# Amplifier.net
KiCad netlist of a schematic drawn in Altium Designer
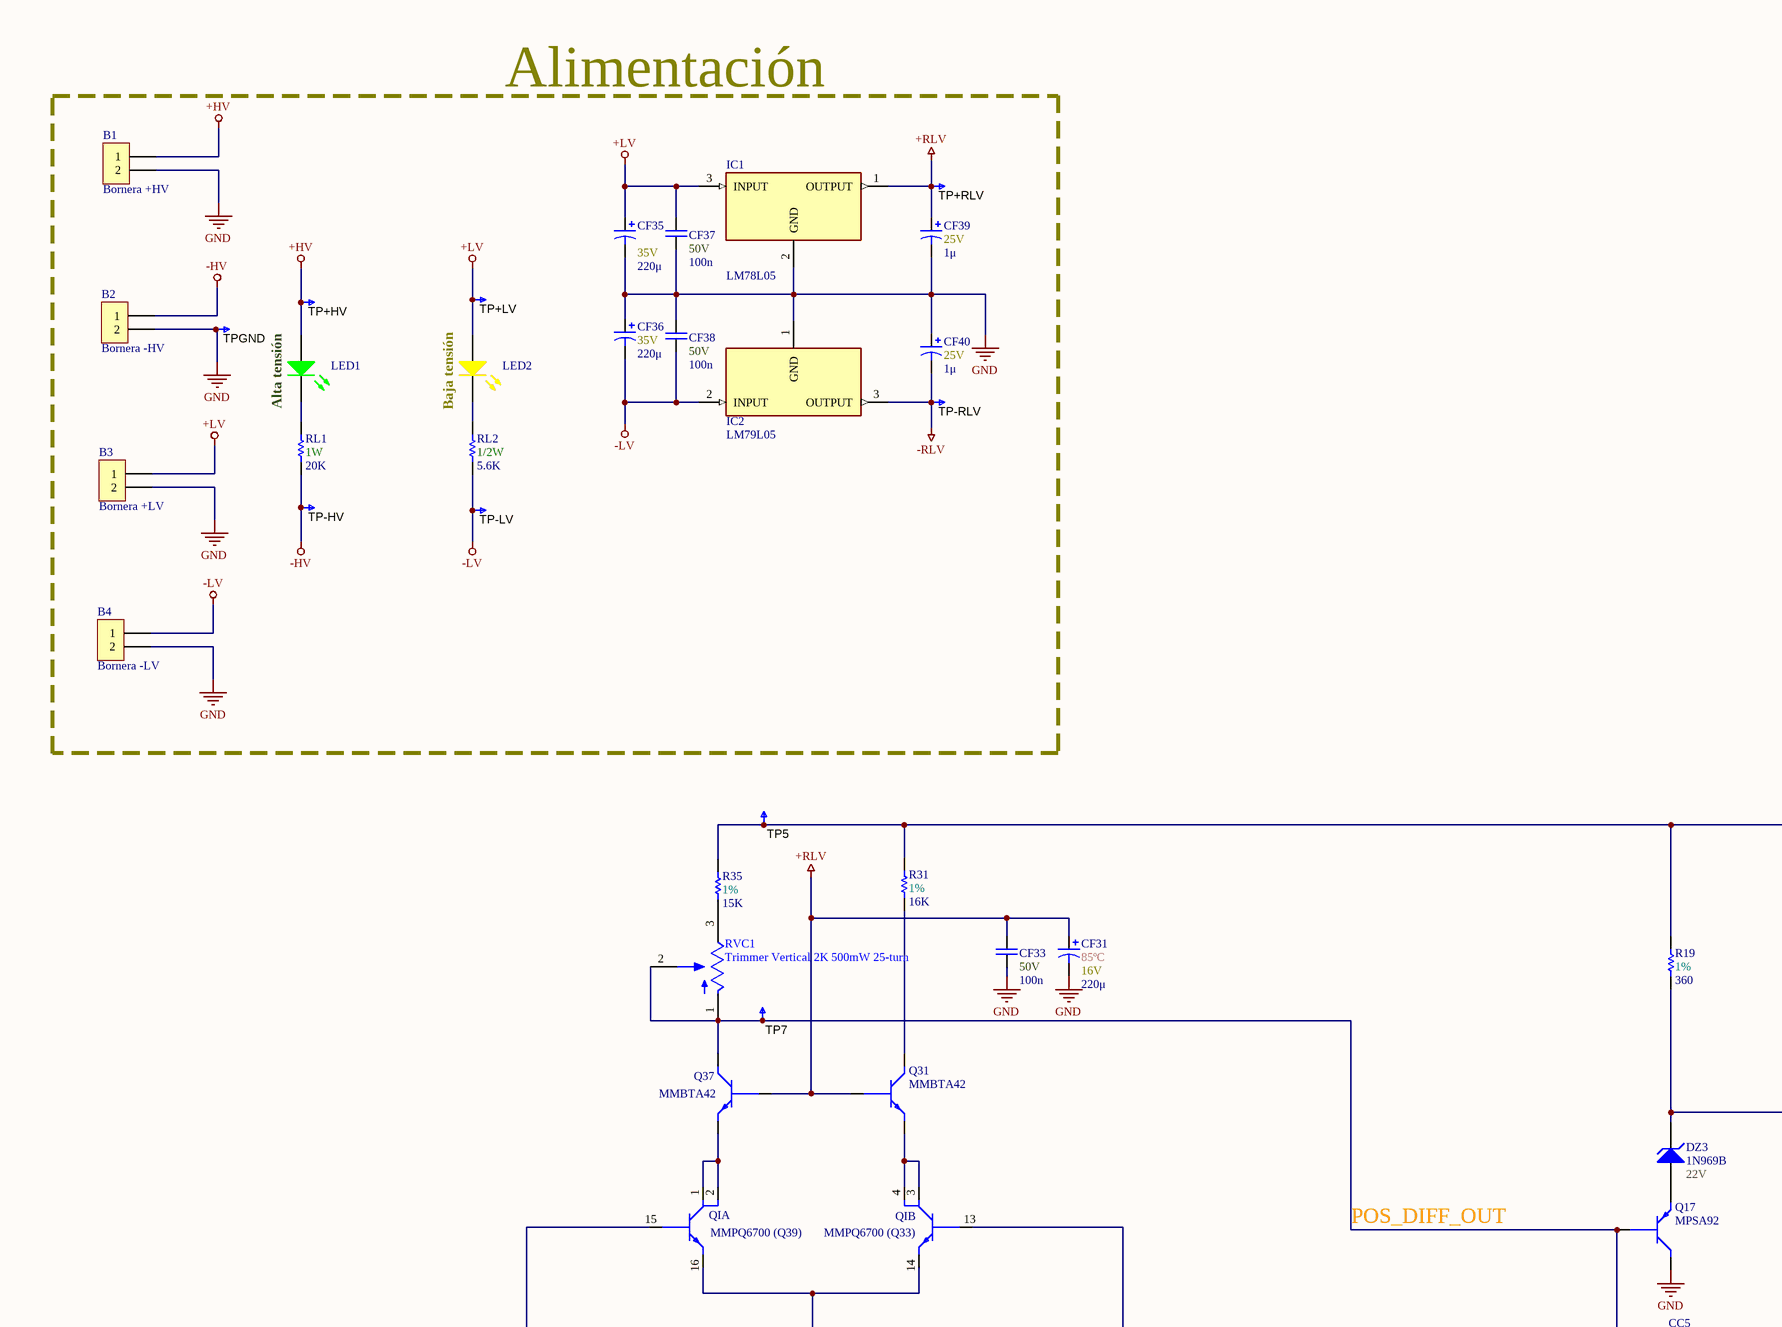
[diagram p0: Amplifier.SchDoc, top left]
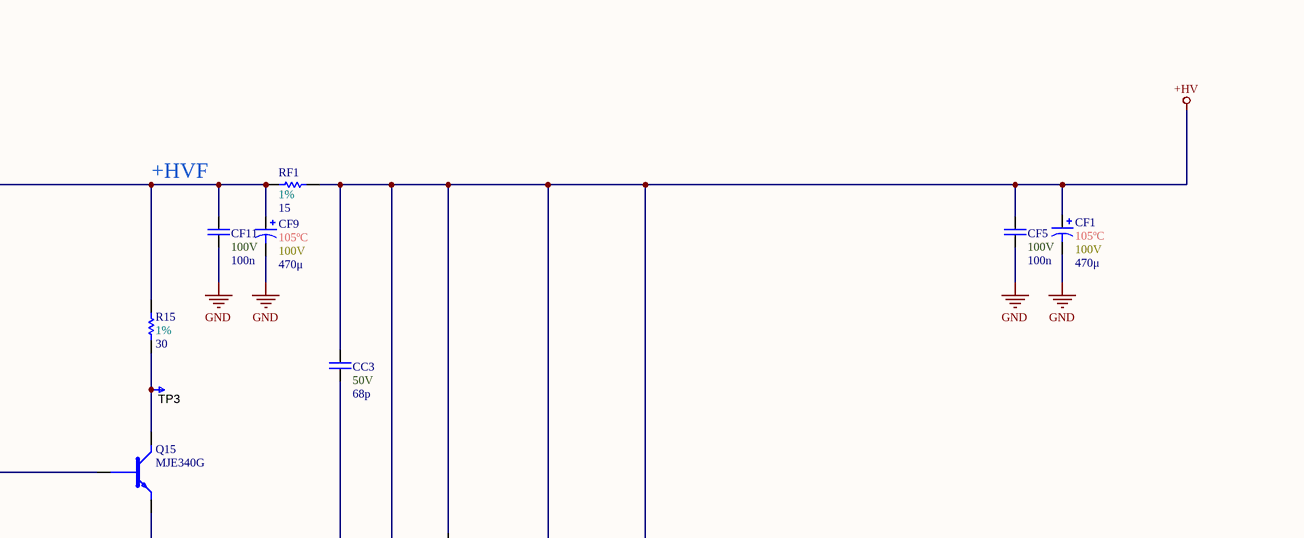
[diagram p1: Amplifier.SchDoc, top right]
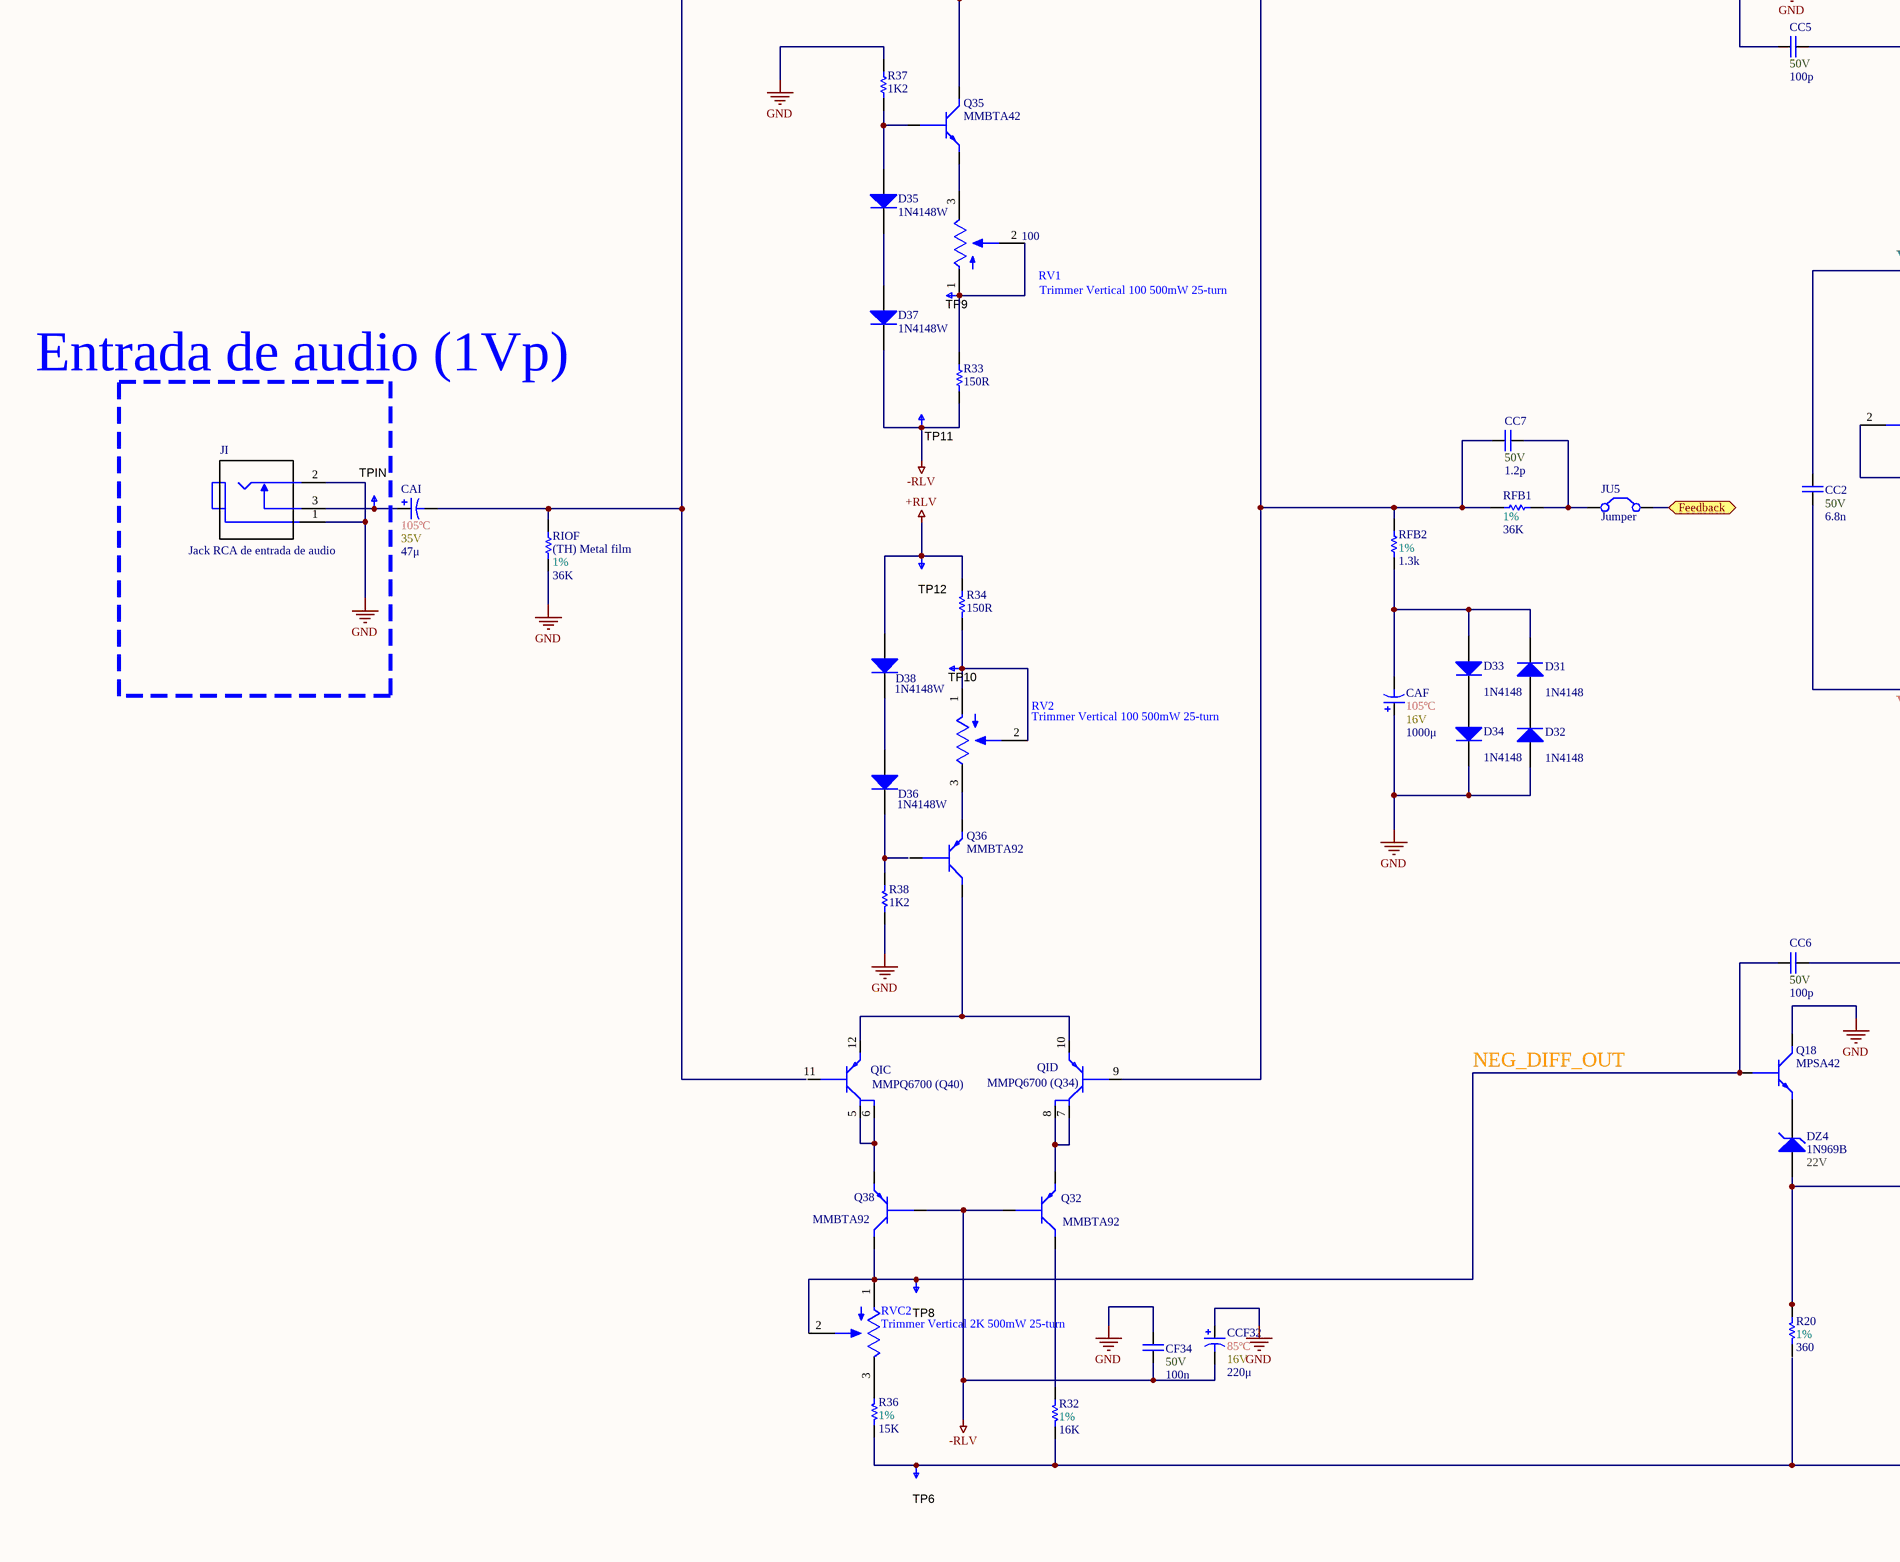
[diagram p2: Amplifier.SchDoc, bottom left]
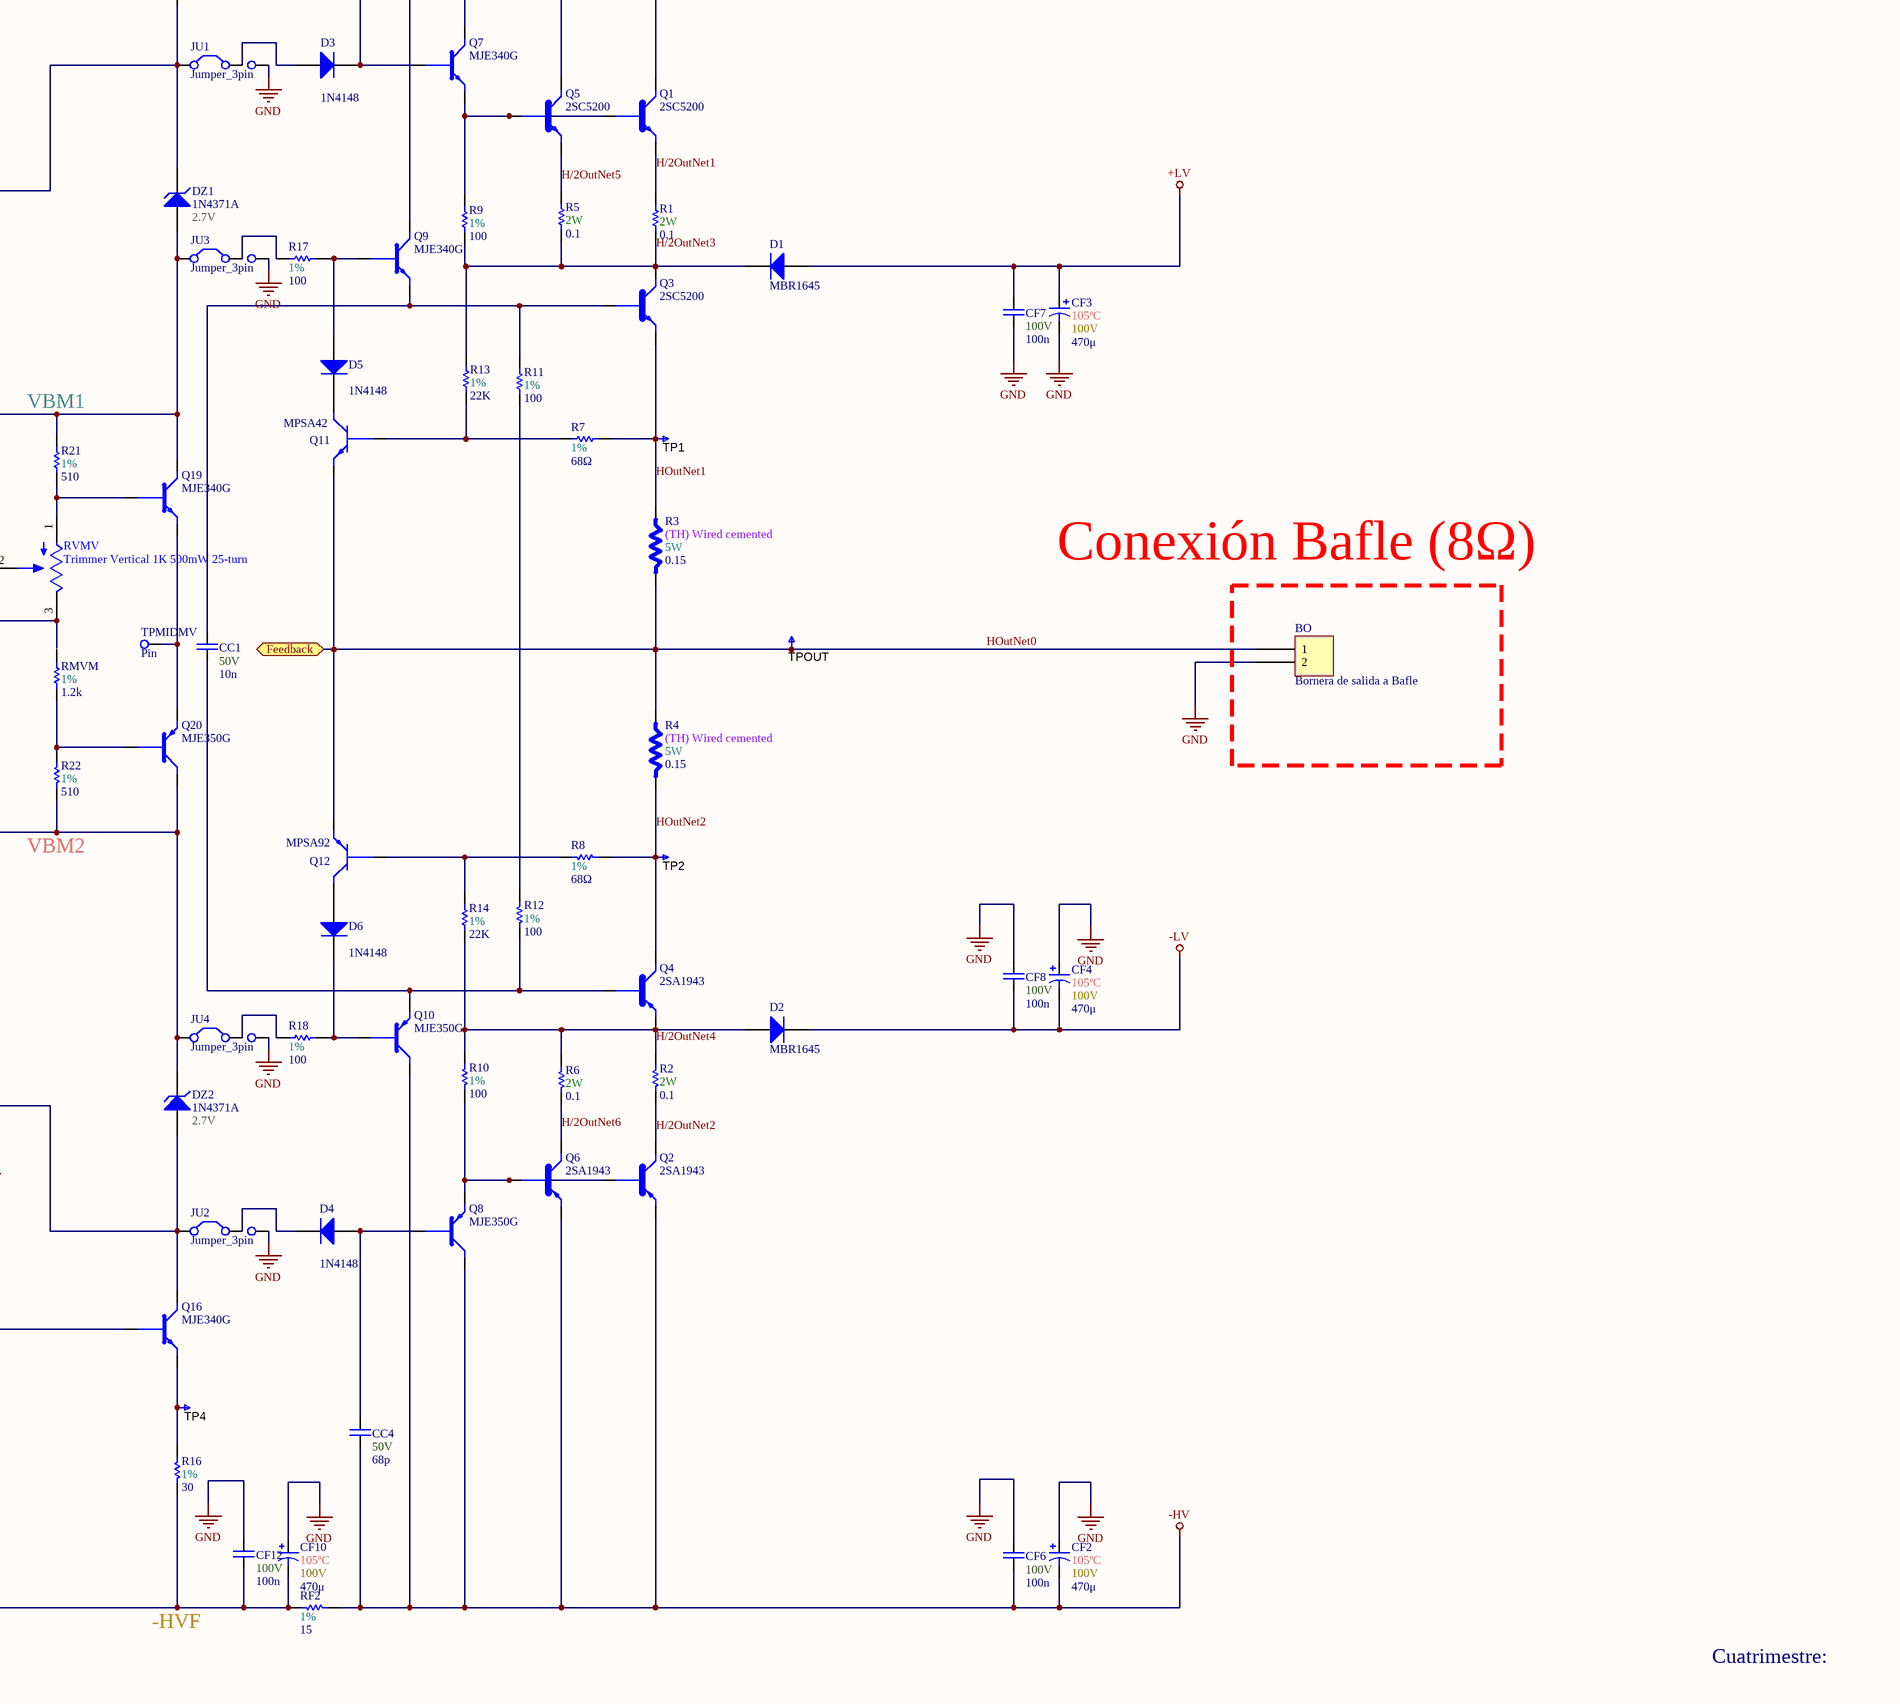
[diagram p3: Amplifier.SchDoc, bottom right]

(export (version "E")
  (design (tool "Eeschema 10.0.6"))
  (components
    (comp (ref "B1")
      (value "Bornera +HV")
      (footprint "TE-C-282822-2-C-PLUGGED")
      (description "TERMI-BLOK HEADER,ASSY90 2P - serie 282822 - 5.00mm")
      (fields (field (name "MANUFACTURER") "TE Connectivity") (field (name "PARTNO") "C-282822-2-C"))
      (libsource (lib "Connectors") (part "C-282822-2-C"))
    )
    (comp (ref "B2")
      (value "Bornera -HV")
      (footprint "TE-C-282822-2-C-PLUGGED")
      (description "TERMI-BLOK HEADER,ASSY90 2P - serie 282822 - 5.00mm")
      (fields (field (name "MANUFACTURER") "TE Connectivity") (field (name "PARTNO") "C-282822-2-C"))
      (libsource (lib "Connectors") (part "C-282822-2-C"))
    )
    (comp (ref "B3")
      (value "Bornera +LV")
      (footprint "TE-C-282822-2-C-PLUGGED")
      (description "TERMI-BLOK HEADER,ASSY90 2P - serie 282822 - 5.00mm")
      (fields (field (name "MANUFACTURER") "TE Connectivity") (field (name "PARTNO") "C-282822-2-C"))
      (libsource (lib "Connectors") (part "C-282822-2-C"))
    )
    (comp (ref "B4")
      (value "Bornera -LV")
      (footprint "TE-C-282822-2-C-PLUGGED")
      (description "TERMI-BLOK HEADER,ASSY90 2P - serie 282822 - 5.00mm")
      (fields (field (name "MANUFACTURER") "TE Connectivity") (field (name "PARTNO") "C-282822-2-C"))
      (libsource (lib "Connectors") (part "C-282822-2-C"))
    )
    (comp (ref "BO")
      (value "Bornera de salida a Bafle")
      (footprint "TE 8PCV-02-006")
      (description "TE Barrier Terminal Block, 2P")
      (fields (field (name "VOLTAGE") "600V"))
      (libsource (lib "Connectors") (part "8PCV-02-006"))
    )
    (comp (ref "CAF")
      (value "1000μ")
      (footprint "Al. Electrolytic 10.0mmx17.0mmx5.0mm-CLEAN")
      (description "Aluminum Electrolytic Capacitor 1000μF 16V 20% 105º")
      (fields
        (field (name "TOLERANCE") "20%")
        (field (name "TEMPERATURE") "105ºC")
        (field (name "VOLTAGE") "16V")
        (field (name "Comment") "Al. Elect. 1000u 16V 20% 105º")
      )
      (libsource (lib "Capacitors") (part "Al. Elect. 1000u 16V 20% 105º"))
    )
    (comp (ref "CAI")
      (value "47μ")
      (footprint "Al. Electrolytic 6.3mmx11.0mmx2.5mm-CLEAN")
      (description "Aluminum Electrolytic Capacitor 47μF 35V 20% 105º")
      (fields
        (field (name "TOLERANCE") "20%")
        (field (name "TEMPERATURE") "105ºC")
        (field (name "VOLTAGE") "35V")
        (field (name "Comment") "Al. Elect. 47u 35V 20% 105º")
      )
      (libsource (lib "Capacitors") (part "Al. Elect. 47u 35V 20% 105º"))
    )
    (comp (ref "CC1")
      (value "10n")
      (footprint "Cer. pitch 5.0mm height 5.5mm")
      (description "Ceramic Capacitor 10nF 50V 10%")
      (fields
        (field (name "TOLERANCE") "10%")
        (field (name "VOLTAGE") "50V")
        (field (name "Comment") "Cer. 10n 50V 10%")
      )
      (libsource (lib "Capacitors") (part "Cer. 10n 50V 10%"))
    )
    (comp (ref "CC2")
      (value "6.8n")
      (footprint "Cer. pitch 2.5mm height 5.0mm")
      (description "Ceramic Capacitor 6.8nF 50V 10%")
      (fields
        (field (name "TOLERANCE") "10%")
        (field (name "VOLTAGE") "50V")
        (field (name "Comment") "Cer. 6.8n 50V 10%")
      )
      (libsource (lib "Capacitors") (part "Cer. 6.8n 50V 10%"))
    )
    (comp (ref "CC3")
      (value "68p")
      (footprint "Cer. pitch 5.08mm height 6.00mm")
      (description "Ceramic Capacitor 68pF 50V 10%")
      (fields
        (field (name "TOLERANCE") "10%")
        (field (name "VOLTAGE") "50V")
        (field (name "Comment") "Cer. 68p 50V 10%")
      )
      (libsource (lib "Capacitors") (part "Cer. 68p 50V 10%"))
    )
    (comp (ref "CC4")
      (value "68p")
      (footprint "Cer. pitch 5.08mm height 6.00mm")
      (description "Ceramic Capacitor 68pF 50V 10%")
      (fields
        (field (name "TOLERANCE") "10%")
        (field (name "VOLTAGE") "50V")
        (field (name "Comment") "Cer. 68p 50V 10%")
      )
      (libsource (lib "Capacitors") (part "Cer. 68p 50V 10%"))
    )
    (comp (ref "CC5")
      (value "100p")
      (footprint "Cer. pitch 5.08mm height 6.00mm")
      (description "Ceramic Capacitor 100pF 50V 10%")
      (fields
        (field (name "TOLERANCE") "10%")
        (field (name "VOLTAGE") "50V")
        (field (name "Comment") "Cer. 100p 50V 10%")
      )
      (libsource (lib "Capacitors") (part "Cer. 100p 50V 10%"))
    )
    (comp (ref "CC6")
      (value "100p")
      (footprint "Cer. pitch 5.08mm height 6.00mm")
      (description "Ceramic Capacitor 100pF 50V 10%")
      (fields
        (field (name "TOLERANCE") "10%")
        (field (name "VOLTAGE") "50V")
        (field (name "Comment") "Cer. 100p 50V 10%")
      )
      (libsource (lib "Capacitors") (part "Cer. 100p 50V 10%"))
    )
    (comp (ref "CC7")
      (value "1.2p")
      (footprint "Cer. pitch 5.08mm height 6.00mm")
      (description "Ceramic Capacitor 1.2pF 50V 10%")
      (fields
        (field (name "TOLERANCE") "10%")
        (field (name "VOLTAGE") "50V")
        (field (name "Comment") "Cer. 1.2p 50V 10%")
      )
      (libsource (lib "Capacitors") (part "Cer. 1.2p 50V 10%"))
    )
    (comp (ref "CCF32")
      (value "220μ")
      (footprint "Al. Electrolytic 6.3mmx12.0mmx2.5mm-CLEAN")
      (description "Aluminum Electrolytic Capacitor 220μF 16V 20% 85º")
      (fields
        (field (name "TOLERANCE") "20%")
        (field (name "TEMPERATURE") "85ºC")
        (field (name "VOLTAGE") "16V")
        (field (name "Comment") "Al. Elect. 220u 16V 20% 85º")
      )
      (libsource (lib "") (part "Al. Elect. 220u 16V 20% 85º_1"))
    )
    (comp (ref "CF1")
      (value "470μ")
      (footprint "Al. Electrolytic 16.0mmx33.0mmx7.5mm-CLEAN")
      (description "Aluminum Electrolytic Capacitor 470μF 100V 20% 105º")
      (fields
        (field (name "TOLERANCE") "20%")
        (field (name "TEMPERATURE") "105ºC")
        (field (name "VOLTAGE") "100V")
        (field (name "Comment") "Al. Elect. 470u 100V 20% 105º")
      )
      (libsource (lib "") (part "Al. Elect. 470u 100V 20% 105º_1"))
    )
    (comp (ref "CF2")
      (value "470μ")
      (footprint "Al. Electrolytic 16.0mmx33.0mmx7.5mm-CLEAN")
      (description "Aluminum Electrolytic Capacitor 470μF 100V 20% 105º")
      (fields
        (field (name "TOLERANCE") "20%")
        (field (name "TEMPERATURE") "105ºC")
        (field (name "VOLTAGE") "100V")
        (field (name "Comment") "Al. Elect. 470u 100V 20% 105º")
      )
      (libsource (lib "Capacitors") (part "Al. Elect. 470u 100V 20% 105º"))
    )
    (comp (ref "CF3")
      (value "470μ")
      (footprint "Al. Electrolytic 16.0mmx33.0mmx7.5mm-CLEAN")
      (description "Aluminum Electrolytic Capacitor 470μF 100V 20% 105º")
      (fields
        (field (name "TOLERANCE") "20%")
        (field (name "TEMPERATURE") "105ºC")
        (field (name "VOLTAGE") "100V")
        (field (name "Comment") "Al. Elect. 470u 100V 20% 105º")
      )
      (libsource (lib "") (part "Al. Elect. 470u 100V 20% 105º_1"))
    )
    (comp (ref "CF4")
      (value "470μ")
      (footprint "Al. Electrolytic 16.0mmx33.0mmx7.5mm-CLEAN")
      (description "Aluminum Electrolytic Capacitor 470μF 100V 20% 105º")
      (fields
        (field (name "TOLERANCE") "20%")
        (field (name "TEMPERATURE") "105ºC")
        (field (name "VOLTAGE") "100V")
        (field (name "Comment") "Al. Elect. 470u 100V 20% 105º")
      )
      (libsource (lib "Capacitors") (part "Al. Elect. 470u 100V 20% 105º"))
    )
    (comp (ref "CF5")
      (value "100n")
      (footprint "Cer. pitch 5.0mm height 6.6mm")
      (description "Polyester Capacitor 100nF 100V 10%")
      (fields
        (field (name "TOLERANCE") "10%")
        (field (name "VOLTAGE") "100V")
        (field (name "Comment") "Poly. 100n 100V 10%")
      )
      (libsource (lib "Capacitors") (part "Poly. 100n 100V 10%"))
    )
    (comp (ref "CF6")
      (value "100n")
      (footprint "Cer. pitch 5.0mm height 6.6mm")
      (description "Polyester Capacitor 100nF 100V 10%")
      (fields
        (field (name "TOLERANCE") "10%")
        (field (name "VOLTAGE") "100V")
        (field (name "Comment") "Poly. 100n 100V 10%")
      )
      (libsource (lib "Capacitors") (part "Poly. 100n 100V 10%"))
    )
    (comp (ref "CF7")
      (value "100n")
      (footprint "Cer. pitch 5.0mm height 6.6mm")
      (description "Polyester Capacitor 100nF 100V 10%")
      (fields
        (field (name "TOLERANCE") "10%")
        (field (name "VOLTAGE") "100V")
        (field (name "Comment") "Poly. 100n 100V 10%")
      )
      (libsource (lib "Capacitors") (part "Poly. 100n 100V 10%"))
    )
    (comp (ref "CF8")
      (value "100n")
      (footprint "Cer. pitch 5.0mm height 6.6mm")
      (description "Polyester Capacitor 100nF 100V 10%")
      (fields
        (field (name "TOLERANCE") "10%")
        (field (name "VOLTAGE") "100V")
        (field (name "Comment") "Poly. 100n 100V 10%")
      )
      (libsource (lib "Capacitors") (part "Poly. 100n 100V 10%"))
    )
    (comp (ref "CF9")
      (value "470μ")
      (footprint "Al. Electrolytic 16.0mmx33.0mmx7.5mm-CLEAN")
      (description "Aluminum Electrolytic Capacitor 470μF 100V 20% 105º")
      (fields
        (field (name "TOLERANCE") "20%")
        (field (name "TEMPERATURE") "105ºC")
        (field (name "VOLTAGE") "100V")
        (field (name "Comment") "Al. Elect. 470u 100V 20% 105º")
      )
      (libsource (lib "") (part "Al. Elect. 470u 100V 20% 105º_1"))
    )
    (comp (ref "CF10")
      (value "470μ")
      (footprint "Al. Electrolytic 16.0mmx33.0mmx7.5mm-CLEAN")
      (description "Aluminum Electrolytic Capacitor 470μF 100V 20% 105º")
      (fields
        (field (name "TOLERANCE") "20%")
        (field (name "TEMPERATURE") "105ºC")
        (field (name "VOLTAGE") "100V")
        (field (name "Comment") "Al. Elect. 470u 100V 20% 105º")
      )
      (libsource (lib "Capacitors") (part "Al. Elect. 470u 100V 20% 105º"))
    )
    (comp (ref "CF11")
      (value "100n")
      (footprint "Cer. pitch 5.0mm height 6.6mm")
      (description "Polyester Capacitor 100nF 100V 10%")
      (fields
        (field (name "TOLERANCE") "10%")
        (field (name "VOLTAGE") "100V")
        (field (name "Comment") "Poly. 100n 100V 10%")
      )
      (libsource (lib "Capacitors") (part "Poly. 100n 100V 10%"))
    )
    (comp (ref "CF12")
      (value "100n")
      (footprint "Cer. pitch 5.0mm height 6.6mm")
      (description "Polyester Capacitor 100nF 100V 10%")
      (fields
        (field (name "TOLERANCE") "10%")
        (field (name "VOLTAGE") "100V")
        (field (name "Comment") "Poly. 100n 100V 10%")
      )
      (libsource (lib "Capacitors") (part "Poly. 100n 100V 10%"))
    )
    (comp (ref "CF31")
      (value "220μ")
      (footprint "Al. Electrolytic 6.3mmx12.0mmx2.5mm-CLEAN")
      (description "Aluminum Electrolytic Capacitor 220μF 16V 20% 85º")
      (fields
        (field (name "TOLERANCE") "20%")
        (field (name "TEMPERATURE") "85ºC")
        (field (name "VOLTAGE") "16V")
        (field (name "Comment") "Al. Elect. 220u 16V 20% 85º")
      )
      (libsource (lib "Capacitors") (part "Al. Elect. 220u 16V 20% 85º"))
    )
    (comp (ref "CF33")
      (value "100n")
      (footprint "Cer. pitch 5.0mm height 5.5mm")
      (description "Ceramic Capacitor 100nF 50V 10%")
      (fields
        (field (name "TOLERANCE") "10%")
        (field (name "VOLTAGE") "50V")
        (field (name "Comment") "Cer. 100n 50V 10%")
      )
      (libsource (lib "Capacitors") (part "Cer. 100n 50V 10%"))
    )
    (comp (ref "CF34")
      (value "100n")
      (footprint "Cer. pitch 5.0mm height 5.5mm")
      (description "Ceramic Capacitor 100nF 50V 10%")
      (fields
        (field (name "TOLERANCE") "10%")
        (field (name "VOLTAGE") "50V")
        (field (name "Comment") "Cer. 100n 50V 10%")
      )
      (libsource (lib "Capacitors") (part "Cer. 100n 50V 10%"))
    )
    (comp (ref "CF35")
      (value "220μ")
      (footprint "Al. Electrolytic 8.0mmx13.0mmx3.5mm-CLEAN")
      (description "Aluminum Electrolytic Capacitor 220μF 35V 20% 105º")
      (fields
        (field (name "TOLERANCE") "20%")
        (field (name "VOLTAGE") "35V")
        (field (name "Comment") "Al. Elect. 220u 35V 20% 105º")
      )
      (libsource (lib "Capacitors") (part "Al. Elect. 220u 35V 20% 105º"))
    )
    (comp (ref "CF36")
      (value "220μ")
      (footprint "Al. Electrolytic 8.0mmx13.0mmx3.5mm-CLEAN")
      (description "Aluminum Electrolytic Capacitor 220μF 35V 20% 105º")
      (fields
        (field (name "TOLERANCE") "20%")
        (field (name "VOLTAGE") "35V")
        (field (name "Comment") "Al. Elect. 220u 35V 20% 105º")
      )
      (libsource (lib "Capacitors") (part "Al. Elect. 220u 35V 20% 105º"))
    )
    (comp (ref "CF37")
      (value "100n")
      (footprint "Cer. pitch 5.0mm height 5.5mm")
      (description "Ceramic Capacitor 100nF 50V 10%")
      (fields
        (field (name "TOLERANCE") "10%")
        (field (name "VOLTAGE") "50V")
        (field (name "Comment") "Cer. 100n 50V 10%")
      )
      (libsource (lib "Capacitors") (part "Cer. 100n 50V 10%"))
    )
    (comp (ref "CF38")
      (value "100n")
      (footprint "Cer. pitch 5.0mm height 5.5mm")
      (description "Ceramic Capacitor 100nF 50V 10%")
      (fields
        (field (name "TOLERANCE") "10%")
        (field (name "VOLTAGE") "50V")
        (field (name "Comment") "Cer. 100n 50V 10%")
      )
      (libsource (lib "Capacitors") (part "Cer. 100n 50V 10%"))
    )
    (comp (ref "CF39")
      (value "1μ")
      (footprint "Tantalum Electrolytic 4.5mmx8.0mmx0.254mm-CLEAN")
      (description "Tantalum Electrolytic Capacitor 1μF 25V 10%")
      (fields
        (field (name "TOLERANCE") "10%")
        (field (name "VOLTAGE") "25V")
        (field (name "Comment") "Tant. Elect. 1u 25V 10%")
      )
      (libsource (lib "Capacitors") (part "Tant. Elect. 1u 25V 10%"))
    )
    (comp (ref "CF40")
      (value "1μ")
      (footprint "Tantalum Electrolytic 4.5mmx8.0mmx0.254mm-CLEAN")
      (description "Tantalum Electrolytic Capacitor 1μF 25V 10%")
      (fields
        (field (name "TOLERANCE") "10%")
        (field (name "VOLTAGE") "25V")
        (field (name "Comment") "Tant. Elect. 1u 25V 10%")
      )
      (libsource (lib "Capacitors") (part "Tant. Elect. 1u 25V 10%"))
    )
    (comp (ref "D1")
      (value "MBR1645")
      (footprint "ONSC-TO-220-2-221B-04")
      (description "45 V, 16 A SWITCHMODE(TM) Schottky Power Rectifier, 2-Pin TO-220, Pb-Free, Tube")
      (libsource (lib "ON Semi Rectifiers") (part "MBR1645"))
    )
    (comp (ref "D2")
      (value "MBR1645")
      (footprint "ONSC-TO-220-2-221B-04")
      (description "45 V, 16 A SWITCHMODE(TM) Schottky Power Rectifier, 2-Pin TO-220, Pb-Free, Tube")
      (libsource (lib "ON Semi Rectifiers") (part "MBR1645"))
    )
    (comp (ref "D3")
      (value "1N4148")
      (footprint "DO-35-0.3mil")
      (description "FAST SWITCHING DIODE")
      (fields
        (field (name "MANUFACTURER") "ON Semiconductors")
        (field (name "POWER") "400mW")
        (field (name "PARTNUMBER") "1N4148")
      )
      (libsource (lib "ON Semi Rectifiers") (part "1N4148"))
    )
    (comp (ref "D4")
      (value "1N4148")
      (footprint "DO-35-0.3mil")
      (description "FAST SWITCHING DIODE")
      (fields
        (field (name "MANUFACTURER") "ON Semiconductors")
        (field (name "POWER") "400mW")
        (field (name "PARTNUMBER") "1N4148")
      )
      (libsource (lib "ON Semi Rectifiers") (part "1N4148"))
    )
    (comp (ref "D5")
      (value "~")
      (footprint "DO-35-0.3mil")
      (description "FAST SWITCHING DIODE")
      (fields
        (field (name "MANUFACTURER") "ON Semiconductors")
        (field (name "POWER") "400mW")
        (field (name "PARTNUMBER") "1N4148")
      )
      (libsource (lib "ON Semi Rectifiers") (part "1N4148"))
    )
    (comp (ref "D6")
      (value "~")
      (footprint "DO-35-0.3mil")
      (description "FAST SWITCHING DIODE")
      (fields
        (field (name "MANUFACTURER") "ON Semiconductors")
        (field (name "POWER") "400mW")
        (field (name "PARTNUMBER") "1N4148")
      )
      (libsource (lib "ON Semi Rectifiers") (part "1N4148"))
    )
    (comp (ref "D31")
      (value "~")
      (footprint "DO-35-0.3mil")
      (description "FAST SWITCHING DIODE")
      (fields
        (field (name "MANUFACTURER") "ON Semiconductors")
        (field (name "POWER") "400mW")
        (field (name "PARTNUMBER") "1N4148")
      )
      (libsource (lib "ON Semi Rectifiers") (part "1N4148"))
    )
    (comp (ref "D32")
      (value "~")
      (footprint "DO-35-0.3mil")
      (description "FAST SWITCHING DIODE")
      (fields
        (field (name "MANUFACTURER") "ON Semiconductors")
        (field (name "POWER") "400mW")
        (field (name "PARTNUMBER") "1N4148")
      )
      (libsource (lib "ON Semi Rectifiers") (part "1N4148"))
    )
    (comp (ref "D33")
      (value "~")
      (footprint "DO-35-0.3mil")
      (description "FAST SWITCHING DIODE")
      (fields
        (field (name "MANUFACTURER") "ON Semiconductors")
        (field (name "POWER") "400mW")
        (field (name "PARTNUMBER") "1N4148")
      )
      (libsource (lib "ON Semi Rectifiers") (part "1N4148"))
    )
    (comp (ref "D34")
      (value "~")
      (footprint "DO-35-0.3mil")
      (description "FAST SWITCHING DIODE")
      (fields
        (field (name "MANUFACTURER") "ON Semiconductors")
        (field (name "POWER") "400mW")
        (field (name "PARTNUMBER") "1N4148")
      )
      (libsource (lib "ON Semi Rectifiers") (part "1N4148"))
    )
    (comp (ref "D35")
      (value "1N4148W")
      (footprint "SOD-123")
      (description "SURFACE MOUNT FAST SWITCHING DIODE")
      (fields (field (name "MANUFACTURER") "Diodes Incorporated") (field (name "POWER") "400mW"))
      (libsource (lib "DIODES_INCROPORATED") (part "1N4148W"))
    )
    (comp (ref "D36")
      (value "1N4148W")
      (footprint "SOD-123")
      (description "SURFACE MOUNT FAST SWITCHING DIODE")
      (fields (field (name "MANUFACTURER") "Diodes Incorporated") (field (name "POWER") "400mW"))
      (libsource (lib "DIODES_INCROPORATED") (part "1N4148W"))
    )
    (comp (ref "D37")
      (value "1N4148W")
      (footprint "SOD-123")
      (description "SURFACE MOUNT FAST SWITCHING DIODE")
      (fields (field (name "MANUFACTURER") "Diodes Incorporated") (field (name "POWER") "400mW"))
      (libsource (lib "DIODES_INCROPORATED") (part "1N4148W"))
    )
    (comp (ref "D38")
      (value "1N4148W")
      (footprint "SOD-123")
      (description "SURFACE MOUNT FAST SWITCHING DIODE")
      (fields (field (name "MANUFACTURER") "Diodes Incorporated") (field (name "POWER") "400mW"))
      (libsource (lib "DIODES_INCROPORATED") (part "1N4148W"))
    )
    (comp (ref "DZ1")
      (value "1N4371A")
      (footprint "DO-35-0.3mil")
      (description "Zener Diode, 2.7V, 500mW")
      (fields
        (field (name "MANUFACTURER") "Microsemi")
        (field (name "POWER") "500mW")
        (field (name "ZV") "2.7V")
        (field (name "PUBLISHER") "Altium Limited")
      )
      (libsource (lib "MICROSEMI") (part "1N4371A"))
    )
    (comp (ref "DZ2")
      (value "1N4371A")
      (footprint "DO-35-0.3mil")
      (description "Zener Diode, 2.7V, 500mW")
      (fields
        (field (name "MANUFACTURER") "Microsemi")
        (field (name "POWER") "500mW")
        (field (name "ZV") "2.7V")
        (field (name "PUBLISHER") "Altium Limited")
      )
      (libsource (lib "MICROSEMI") (part "1N4371A"))
    )
    (comp (ref "DZ3")
      (value "1N969B")
      (footprint "DO-35-0.3mil")
      (description "Zener Diode, 22V, 500mW")
      (fields
        (field (name "MANUFACTURER") "Microsemi")
        (field (name "POWER") "500mW")
        (field (name "ZV") "22V")
        (field (name "PUBLISHER") "Altium Limited")
      )
      (libsource (lib "MICROSEMI") (part "1N969B"))
    )
    (comp (ref "DZ4")
      (value "1N969B")
      (footprint "DO-35-0.3mil")
      (description "Zener Diode, 22V, 500mW")
      (fields
        (field (name "MANUFACTURER") "Microsemi")
        (field (name "POWER") "500mW")
        (field (name "ZV") "22V")
        (field (name "PUBLISHER") "Altium Limited")
      )
      (libsource (lib "MICROSEMI") (part "1N969B"))
    )
    (comp (ref "IC1")
      (value "LM78L05")
      (footprint "TO-92-1")
      (description "5V fixed regulator - 100mA")
      (fields (field (name "MANUFACTURER_PART_NUMBER") "LM7805"))
      (libsource (lib "FIXED_REGULATORS") (part "LM78L05"))
    )
    (comp (ref "IC2")
      (value "LM79L05")
      (footprint "TO-92-1")
      (description "-5V fixed regulator - 100mA")
      (fields (field (name "MANUFACTURER_PART_NUMBER") "LM7805"))
      (libsource (lib "FIXED_REGULATORS") (part "LM79L05"))
    )
    (comp (ref "JI")
      (value "Jack RCA de entrada de audio")
      (footprint "*SWITCHCRAFT_PJRAN1X1U01X")
      (description "Conn Phono Jack F 3 POS Solder RA Thru-Hole 3 Terminal 1 Port")
      (fields (field (name "MP") "PJRAN1X1U01X") (field (name "MF") "Switchcraft"))
      (libsource (lib "Connectors") (part "PJRAN1X1U01X"))
    )
    (comp (ref "JU1")
      (value "Jumper_3pin")
      (footprint "Jumper 200mil 3 pin")
      (description "Jumper Wire")
      (fields (field (name "PUBLISHER") "Altium Limited"))
      (libsource (lib "Test Points and Jumpers") (part "Jumper_3pin"))
    )
    (comp (ref "JU2")
      (value "Jumper_3pin")
      (footprint "Jumper 200mil 3 pin")
      (description "Jumper Wire")
      (fields (field (name "PUBLISHER") "Altium Limited"))
      (libsource (lib "Test Points and Jumpers") (part "Jumper_3pin"))
    )
    (comp (ref "JU3")
      (value "Jumper_3pin")
      (footprint "Jumper 200mil 3 pin")
      (description "Jumper Wire")
      (fields (field (name "PUBLISHER") "Altium Limited"))
      (libsource (lib "Test Points and Jumpers") (part "Jumper_3pin"))
    )
    (comp (ref "JU4")
      (value "Jumper_3pin")
      (footprint "Jumper 200mil 3 pin")
      (description "Jumper Wire")
      (fields (field (name "PUBLISHER") "Altium Limited"))
      (libsource (lib "Test Points and Jumpers") (part "Jumper_3pin"))
    )
    (comp (ref "JU5")
      (value "Jumper")
      (footprint "Jumper 200mil 2 pin")
      (description "Jumper Wire")
      (fields (field (name "PUBLISHER") "Altium Limited"))
      (libsource (lib "Test Points and Jumpers") (part "Jumper"))
    )
    (comp (ref "LED1")
      (value "Alta tensión")
      (footprint "LED_5MM_GREEN")
      (description "Typical LED (GREEN)")
      (fields (field (name "PUBLISHER") "Altium Limited"))
      (libsource (lib "GENERIC_LED") (part "LED (GREEN)"))
    )
    (comp (ref "LED2")
      (value "Baja tensión")
      (footprint "LED_5MM_YELLOW")
      (description "Typical LED (YELLOW)")
      (fields (field (name "PUBLISHER") "Altium Limited"))
      (libsource (lib "GENERIC_LED") (part "LED (YELLOW)"))
    )
    (comp (ref "Q1")
      (value "2SC5200")
      (footprint "TO-264-3")
      (description "Transistor GP BJT NPN 230V 15A 3-Pin_3+Tab_ TO-264 Tube")
      (fields (field (name "MANUFACTURER") "Toshiba") (field (name "POWER") "150W"))
      (libsource (lib "TOSHIBA") (part "2SC5200"))
    )
    (comp (ref "Q2")
      (value "2SA1943")
      (footprint "TO-264-3")
      (description "Transistor GP BJT PNP 230V 15A 3-Pin_3+Tab_ TO-264 Tube")
      (fields (field (name "MANUFACTURER") "Toshiba") (field (name "POWER") "150W"))
      (libsource (lib "TOSHIBA") (part "2SA1943"))
    )
    (comp (ref "Q3")
      (value "2SC5200")
      (footprint "TO-264-3")
      (description "Transistor GP BJT NPN 230V 15A 3-Pin_3+Tab_ TO-264 Tube")
      (fields (field (name "MANUFACTURER") "Toshiba") (field (name "POWER") "150W"))
      (libsource (lib "TOSHIBA") (part "2SC5200"))
    )
    (comp (ref "Q4")
      (value "2SA1943")
      (footprint "TO-264-3")
      (description "Transistor GP BJT PNP 230V 15A 3-Pin_3+Tab_ TO-264 Tube")
      (fields (field (name "MANUFACTURER") "Toshiba") (field (name "POWER") "150W"))
      (libsource (lib "TOSHIBA") (part "2SA1943"))
    )
    (comp (ref "Q5")
      (value "2SC5200")
      (footprint "TO-264-3")
      (description "Transistor GP BJT NPN 230V 15A 3-Pin_3+Tab_ TO-264 Tube")
      (fields (field (name "MANUFACTURER") "Toshiba") (field (name "POWER") "150W"))
      (libsource (lib "TOSHIBA") (part "2SC5200"))
    )
    (comp (ref "Q6")
      (value "2SA1943")
      (footprint "TO-264-3")
      (description "Transistor GP BJT PNP 230V 15A 3-Pin_3+Tab_ TO-264 Tube")
      (fields (field (name "MANUFACTURER") "Toshiba") (field (name "POWER") "150W"))
      (libsource (lib "TOSHIBA") (part "2SA1943"))
    )
    (comp (ref "Q7")
      (value "MJE340G")
      (footprint "TO-225")
      (description "Plastic Medium-Power NPN Silicon Transistor, 300 VOLTS, 0.5 AMPERE, 20 WATTS")
      (fields (field (name "MANUFACTURER") "ON Semiconductor") (field (name "POWER") "20W"))
      (libsource (lib "ON Semi Transistors") (part "MJE340G"))
    )
    (comp (ref "Q8")
      (value "MJE350G")
      (footprint "TO-225")
      (description "Plastic Medium-Power PNP Silicon Transistor, 300 VOLTS, 0.5 AMPERE, 20 WATTS")
      (fields (field (name "MANUFACTURER") "ON Semiconductor") (field (name "POWER") "20W"))
      (libsource (lib "ON Semi Transistors") (part "MJE350G"))
    )
    (comp (ref "Q9")
      (value "MJE340G")
      (footprint "TO-225")
      (description "Plastic Medium-Power NPN Silicon Transistor, 300 VOLTS, 0.5 AMPERE, 20 WATTS")
      (fields (field (name "MANUFACTURER") "ON Semiconductor") (field (name "POWER") "20W"))
      (libsource (lib "ON Semi Transistors") (part "MJE340G"))
    )
    (comp (ref "Q10")
      (value "MJE350G")
      (footprint "TO-225")
      (description "Plastic Medium-Power PNP Silicon Transistor, 300 VOLTS, 0.5 AMPERE, 20 WATTS")
      (fields (field (name "MANUFACTURER") "ON Semiconductor") (field (name "POWER") "20W"))
      (libsource (lib "ON Semi Transistors") (part "MJE350G"))
    )
    (comp (ref "Q11")
      (value "MPSA42")
      (footprint "TO-92-1")
      (description "High Voltage NPN Bipolar Transistor")
      (fields (field (name "MANUFACTURER") "ON Semiconductor") (field (name "PARTNUMBER") "MJE340G"))
      (libsource (lib "ON Semi Transistors") (part "MPSA42"))
    )
    (comp (ref "Q12")
      (value "MPSA92")
      (footprint "TO-92-1")
      (description "High Voltage PNP Bipolar Transistor")
      (fields (field (name "MANUFACTURER") "ON Semiconductor") (field (name "PARTNUMBER") "MJE340G"))
      (libsource (lib "ON Semi Transistors") (part "MPSA92"))
    )
    (comp (ref "Q15")
      (value "MJE340G")
      (footprint "TO-225")
      (description "Plastic Medium-Power NPN Silicon Transistor, 300 VOLTS, 0.5 AMPERE, 20 WATTS")
      (fields (field (name "MANUFACTURER") "ON Semiconductor") (field (name "POWER") "20W"))
      (libsource (lib "ON Semi Transistors") (part "MJE340G"))
    )
    (comp (ref "Q16")
      (value "MJE340G")
      (footprint "TO-225")
      (description "Plastic Medium-Power NPN Silicon Transistor, 300 VOLTS, 0.5 AMPERE, 20 WATTS")
      (fields (field (name "MANUFACTURER") "ON Semiconductor") (field (name "POWER") "20W"))
      (libsource (lib "ON Semi Transistors") (part "MJE340G"))
    )
    (comp (ref "Q17")
      (value "MPSA92")
      (footprint "TO-92-1")
      (description "High Voltage PNP Bipolar Transistor")
      (fields (field (name "MANUFACTURER") "ON Semiconductor") (field (name "PARTNUMBER") "MJE340G"))
      (libsource (lib "ON Semi Transistors") (part "MPSA92"))
    )
    (comp (ref "Q18")
      (value "MPSA42")
      (footprint "TO-92-1")
      (description "High Voltage NPN Bipolar Transistor")
      (fields (field (name "MANUFACTURER") "ON Semiconductor") (field (name "PARTNUMBER") "MJE340G"))
      (libsource (lib "ON Semi Transistors") (part "MPSA42"))
    )
    (comp (ref "Q19")
      (value "MJE340G")
      (footprint "TO-225")
      (description "Plastic Medium-Power NPN Silicon Transistor, 300 VOLTS, 0.5 AMPERE, 20 WATTS")
      (fields (field (name "MANUFACTURER") "ON Semiconductor") (field (name "POWER") "20W"))
      (libsource (lib "ON Semi Transistors") (part "MJE340G"))
    )
    (comp (ref "Q20")
      (value "MJE350G")
      (footprint "TO-225")
      (description "Plastic Medium-Power PNP Silicon Transistor, 300 VOLTS, 0.5 AMPERE, 20 WATTS")
      (fields (field (name "MANUFACTURER") "ON Semiconductor") (field (name "POWER") "20W"))
      (libsource (lib "ON Semi Transistors") (part "MJE350G"))
    )
    (comp (ref "Q31")
      (value "MMBTA42")
      (footprint "SOT-23")
      (description "High Voltage NPN Bipolar Transistor")
      (fields (field (name "MANUFACTURER") "ON Semiconductor") (field (name "PARTNUMBER") "MJE340G"))
      (libsource (lib "ON Semi Transistors") (part "MMBTA42"))
    )
    (comp (ref "Q32")
      (value "MMBTA92")
      (footprint "SOT-23")
      (description "High Voltage PNP Bipolar Transistor")
      (fields (field (name "MANUFACTURER") "ON Semiconductor") (field (name "PARTNUMBER") "MJE340G"))
      (libsource (lib "ON Semi Transistors") (part "MMBTA92"))
    )
    (comp (ref "Q35")
      (value "MMBTA42")
      (footprint "SOT-23")
      (description "High Voltage NPN Bipolar Transistor")
      (fields (field (name "MANUFACTURER") "ON Semiconductor") (field (name "PARTNUMBER") "MJE340G"))
      (libsource (lib "ON Semi Transistors") (part "MMBTA42"))
    )
    (comp (ref "Q36")
      (value "MMBTA92")
      (footprint "SOT-23")
      (description "High Voltage PNP Bipolar Transistor")
      (fields (field (name "MANUFACTURER") "ON Semiconductor") (field (name "PARTNUMBER") "MJE340G"))
      (libsource (lib "ON Semi Transistors") (part "MMBTA92"))
    )
    (comp (ref "Q37")
      (value "MMBTA42")
      (footprint "SOT-23")
      (description "High Voltage NPN Bipolar Transistor")
      (fields (field (name "MANUFACTURER") "ON Semiconductor") (field (name "PARTNUMBER") "MJE340G"))
      (libsource (lib "ON Semi Transistors") (part "MMBTA42"))
    )
    (comp (ref "Q38")
      (value "MMBTA92")
      (footprint "SOT-23")
      (description "High Voltage PNP Bipolar Transistor")
      (fields (field (name "MANUFACTURER") "ON Semiconductor") (field (name "PARTNUMBER") "MJE340G"))
      (libsource (lib "ON Semi Transistors") (part "MMBTA92"))
    )
    (comp (ref "QI")
      (value "MMPQ6700 (Q39)")
      (footprint "SOIC-16L")
      (description "Quad NPN and PNP General-Purpose Amplifier")
      (fields (field (name "MANUFACTURER") "ON Semiconductor") (field (name "PARTNUMBER") "MMPQ6700"))
      (libsource (lib "ON Semi Transistors") (part "MMPQ6700"))
    )
    (comp (ref "R1")
      (value "0.1")
      (footprint "AXIAL-0.6-E24-2W-0.1")
      (description "Resistor 0.1Ω 2W 5%")
      (fields
        (field (name "TOLERANCE") "5%")
        (field (name "POWER") "2W")
        (field (name "Comment") "Resistor 0.1 2W 5%")
      )
      (libsource (lib "Resistors") (part "Resistor 0.1 2W 5%"))
    )
    (comp (ref "R2")
      (value "0.1")
      (footprint "AXIAL-0.6-E24-2W-0.1")
      (description "Resistor 0.1Ω 2W 5%")
      (fields
        (field (name "TOLERANCE") "5%")
        (field (name "POWER") "2W")
        (field (name "Comment") "Resistor 0.1 2W 5%")
      )
      (libsource (lib "Resistors") (part "Resistor 0.1 2W 5%"))
    )
    (comp (ref "R3")
      (value "0.15")
      (footprint "Cemented resistor 0.15 5W 5%")
      (description "Cemented resistor 0.15Ω 5% 5W")
      (fields
        (field (name "TOLERANCE") "5%")
        (field (name "TYPE") "(TH) Wired cemented")
        (field (name "POWER") "5W")
        (field (name "Comment") "Cemented resistor 0.15 5W 5%")
      )
      (libsource (lib "Resistors") (part "Cemented resistor 0.15 5W 5%"))
    )
    (comp (ref "R4")
      (value "0.15")
      (footprint "Cemented resistor 0.15 5W 5%")
      (description "Cemented resistor 0.15Ω 5% 5W")
      (fields
        (field (name "TOLERANCE") "5%")
        (field (name "TYPE") "(TH) Wired cemented")
        (field (name "POWER") "5W")
        (field (name "Comment") "Cemented resistor 0.15 5W 5%")
      )
      (libsource (lib "Resistors") (part "Cemented resistor 0.15 5W 5%"))
    )
    (comp (ref "R5")
      (value "0.1")
      (footprint "AXIAL-0.6-E24-2W-0.1")
      (description "Resistor 0.1Ω 2W 5%")
      (fields
        (field (name "TOLERANCE") "5%")
        (field (name "POWER") "2W")
        (field (name "Comment") "Resistor 0.1 2W 5%")
      )
      (libsource (lib "Resistors") (part "Resistor 0.1 2W 5%"))
    )
    (comp (ref "R6")
      (value "0.1")
      (footprint "AXIAL-0.6-E24-2W-0.1")
      (description "Resistor 0.1Ω 2W 5%")
      (fields
        (field (name "TOLERANCE") "5%")
        (field (name "POWER") "2W")
        (field (name "Comment") "Resistor 0.1 2W 5%")
      )
      (libsource (lib "Resistors") (part "Resistor 0.1 2W 5%"))
    )
    (comp (ref "R7")
      (value "68Ω")
      (footprint "AXIAL-0.4-E24-0_25W-68-1%")
      (description "Resistor 68Ω 1/4W 1%")
      (fields
        (field (name "POWER") "1/4W")
        (field (name "TOLERANCE") "1%")
        (field (name "Comment") "Resistor 68 1/4W 1%")
      )
      (libsource (lib "Resistors") (part "Resistor 68 1/4W 1%"))
    )
    (comp (ref "R8")
      (value "68Ω")
      (footprint "AXIAL-0.4-E24-0_25W-68-1%")
      (description "Resistor 68Ω 1/4W 1%")
      (fields
        (field (name "POWER") "1/4W")
        (field (name "TOLERANCE") "1%")
        (field (name "Comment") "Resistor 68 1/4W 1%")
      )
      (libsource (lib "Resistors") (part "Resistor 68 1/4W 1%"))
    )
    (comp (ref "R9")
      (value "100")
      (footprint "AXIAL-0.4-E24-0_25W-100-1%")
      (description "Resistor 100Ω 1/4W 1%")
      (fields
        (field (name "POWER") "1/4W")
        (field (name "TOLERANCE") "1%")
        (field (name "Comment") "Resistor 100 1/4W 1%")
      )
      (libsource (lib "Resistors") (part "Resistor 100 1/4W 1%"))
    )
    (comp (ref "R10")
      (value "100")
      (footprint "AXIAL-0.4-E24-0_25W-100-1%")
      (description "Resistor 100Ω 1/4W 1%")
      (fields
        (field (name "POWER") "1/4W")
        (field (name "TOLERANCE") "1%")
        (field (name "Comment") "Resistor 100 1/4W 1%")
      )
      (libsource (lib "Resistors") (part "Resistor 100 1/4W 1%"))
    )
    (comp (ref "R11")
      (value "100")
      (footprint "AXIAL-0.4-E24-0_25W-100-1%")
      (description "Resistor 100Ω 1/4W 1%")
      (fields
        (field (name "POWER") "1/4W")
        (field (name "TOLERANCE") "1%")
        (field (name "Comment") "Resistor 100 1/4W 1%")
      )
      (libsource (lib "Resistors") (part "Resistor 100 1/4W 1%"))
    )
    (comp (ref "R12")
      (value "100")
      (footprint "AXIAL-0.4-E24-0_25W-100-1%")
      (description "Resistor 100Ω 1/4W 1%")
      (fields
        (field (name "POWER") "1/4W")
        (field (name "TOLERANCE") "1%")
        (field (name "Comment") "Resistor 100 1/4W 1%")
      )
      (libsource (lib "Resistors") (part "Resistor 100 1/4W 1%"))
    )
    (comp (ref "R13")
      (value "22K")
      (footprint "AXIAL-0.4-E24-0_25W-22k-1%")
      (description "Resistor 22KΩ 1/4W 1%")
      (fields
        (field (name "POWER") "1/4W")
        (field (name "TOLERANCE") "1%")
        (field (name "Comment") "Resistor 22K 1/4W 1%")
      )
      (libsource (lib "Resistors") (part "Resistor 22K 1/4W 1%"))
    )
    (comp (ref "R14")
      (value "22K")
      (footprint "AXIAL-0.4-E24-0_25W-22k-1%")
      (description "Resistor 22KΩ 1/4W 1%")
      (fields
        (field (name "POWER") "1/4W")
        (field (name "TOLERANCE") "1%")
        (field (name "Comment") "Resistor 22K 1/4W 1%")
      )
      (libsource (lib "Resistors") (part "Resistor 22K 1/4W 1%"))
    )
    (comp (ref "R15")
      (value "30")
      (footprint "AXIAL-0.4-E24-0_25W-30-1%")
      (description "Resistor 30Ω 1/4W 1%")
      (fields
        (field (name "POWER") "1/4W")
        (field (name "TOLERANCE") "1%")
        (field (name "Comment") "Resistor 30 1/4W 1%")
      )
      (libsource (lib "Resistors") (part "Resistor 30 1/4W 1%"))
    )
    (comp (ref "R16")
      (value "30")
      (footprint "AXIAL-0.4-E24-0_25W-30-1%")
      (description "Resistor 30Ω 1/4W 1%")
      (fields
        (field (name "POWER") "1/4W")
        (field (name "TOLERANCE") "1%")
        (field (name "Comment") "Resistor 30 1/4W 1%")
      )
      (libsource (lib "Resistors") (part "Resistor 30 1/4W 1%"))
    )
    (comp (ref "R17")
      (value "100")
      (footprint "AXIAL-0.4-E24-0_25W-100-1%")
      (description "Resistor 100Ω 1/4W 1%")
      (fields
        (field (name "POWER") "1/4W")
        (field (name "TOLERANCE") "1%")
        (field (name "Comment") "Resistor 100 1/4W 1%")
      )
      (libsource (lib "Resistors") (part "Resistor 100 1/4W 1%"))
    )
    (comp (ref "R18")
      (value "100")
      (footprint "AXIAL-0.4-E24-0_25W-100-1%")
      (description "Resistor 100Ω 1/4W 1%")
      (fields
        (field (name "POWER") "1/4W")
        (field (name "TOLERANCE") "1%")
        (field (name "Comment") "Resistor 100 1/4W 1%")
      )
      (libsource (lib "Resistors") (part "Resistor 100 1/4W 1%"))
    )
    (comp (ref "R19")
      (value "360")
      (footprint "AXIAL-0.4-E24-0_25W-360-1%")
      (description "Resistor 360Ω 1/4W 1%")
      (fields
        (field (name "POWER") "1/4W")
        (field (name "TOLERANCE") "1%")
        (field (name "Comment") "Resistor 360 1/4W 1%")
      )
      (libsource (lib "Resistors") (part "Resistor 360 1/4W 1%"))
    )
    (comp (ref "R20")
      (value "360")
      (footprint "AXIAL-0.4-E24-0_25W-360-1%")
      (description "Resistor 360Ω 1/4W 1%")
      (fields
        (field (name "POWER") "1/4W")
        (field (name "TOLERANCE") "1%")
        (field (name "Comment") "Resistor 360 1/4W 1%")
      )
      (libsource (lib "Resistors") (part "Resistor 360 1/4W 1%"))
    )
    (comp (ref "R21")
      (value "510")
      (footprint "AXIAL-0.4-E24-0_25W-510-1%")
      (description "Resistor 510Ω 1/4W 1%")
      (fields
        (field (name "POWER") "1/4W")
        (field (name "TOLERANCE") "1%")
        (field (name "Comment") "Resistor 510 1/4W 1%")
      )
      (libsource (lib "Resistors") (part "Resistor 510 1/4W 1%"))
    )
    (comp (ref "R22")
      (value "510")
      (footprint "AXIAL-0.4-E24-0_25W-510-1%")
      (description "Resistor 510Ω 1/4W 1%")
      (fields
        (field (name "POWER") "1/4W")
        (field (name "TOLERANCE") "1%")
        (field (name "Comment") "Resistor 510 1/4W 1%")
      )
      (libsource (lib "Resistors") (part "Resistor 510 1/4W 1%"))
    )
    (comp (ref "R31")
      (value "16K")
      (footprint "AXIAL-0.4-E24-0_25W-16k-1%")
      (description "Resistor 16KΩ 1/4W 1%")
      (fields
        (field (name "POWER") "1/4W")
        (field (name "TOLERANCE") "1%")
        (field (name "Comment") "Resistor 16K 1/4W 1%")
      )
      (libsource (lib "Resistors") (part "Resistor 16K 1/4W 1%"))
    )
    (comp (ref "R32")
      (value "16K")
      (footprint "AXIAL-0.4-E24-0_25W-16k-1%")
      (description "Resistor 16KΩ 1/4W 1%")
      (fields
        (field (name "POWER") "1/4W")
        (field (name "TOLERANCE") "1%")
        (field (name "Comment") "Resistor 16K 1/4W 1%")
      )
      (libsource (lib "Resistors") (part "Resistor 16K 1/4W 1%"))
    )
    (comp (ref "R33")
      (value "150R")
      (footprint "RES_SM0805_YAGEORC_N")
      (description "RES 150R SM0805 YAGEO RC_L")
      (fields
        (field (name "MANUFACTURER") "Yageo")
        (field (name "MANUFACTURER PART NUMBER") "RC0805FR-07150RL")
      )
      (libsource (lib "Yageo_SMD_passives_") (part "RC0805FR-07150RL"))
    )
    (comp (ref "R34")
      (value "150R")
      (footprint "RES_SM0805_YAGEORC_N")
      (description "RES 150R SM0805 YAGEO RC_L")
      (fields
        (field (name "MANUFACTURER") "Yageo")
        (field (name "MANUFACTURER PART NUMBER") "RC0805FR-07150RL")
      )
      (libsource (lib "Yageo_SMD_passives_") (part "RC0805FR-07150RL"))
    )
    (comp (ref "R35")
      (value "15K")
      (footprint "AXIAL-0.4-E24-0_25W-15k-1%")
      (description "Resistor 15KΩ 1/4W 1%")
      (fields
        (field (name "POWER") "1/4W")
        (field (name "TOLERANCE") "1%")
        (field (name "Comment") "Resistor 15K 1/4W 1%")
      )
      (libsource (lib "Resistors") (part "Resistor 15K 1/4W 1%"))
    )
    (comp (ref "R36")
      (value "15K")
      (footprint "AXIAL-0.4-E24-0_25W-15k-1%")
      (description "Resistor 15KΩ 1/4W 1%")
      (fields
        (field (name "POWER") "1/4W")
        (field (name "TOLERANCE") "1%")
        (field (name "Comment") "Resistor 15K 1/4W 1%")
      )
      (libsource (lib "Resistors") (part "Resistor 15K 1/4W 1%"))
    )
    (comp (ref "R37")
      (value "1K2")
      (footprint "RES_SM0603_YAGEORC_N")
      (description "RES 1K2 SM0603 YAGEO RC_L")
      (fields
        (field (name "MANUFACTURER") "Yageo")
        (field (name "MANUFACTURER PART NUMBER") "RC0603FR-071K2L")
      )
      (libsource (lib "Yageo_SMD_passives_") (part "RC0603FR-071K2L"))
    )
    (comp (ref "R38")
      (value "1K2")
      (footprint "RES_SM0603_YAGEORC_N")
      (description "RES 1K2 SM0603 YAGEO RC_L")
      (fields
        (field (name "MANUFACTURER") "Yageo")
        (field (name "MANUFACTURER PART NUMBER") "RC0603FR-071K2L")
      )
      (libsource (lib "Yageo_SMD_passives_") (part "RC0603FR-071K2L"))
    )
    (comp (ref "RF1")
      (value "15")
      (footprint "AXIAL-0.4-E24-0_25W-15-1%")
      (description "Resistor 15Ω 1/4W 1%")
      (fields
        (field (name "POWER") "1/4W")
        (field (name "TOLERANCE") "1%")
        (field (name "Comment") "Resistor 15 1/4W 1%")
      )
      (libsource (lib "Resistors") (part "Resistor 15 1/4W 1%"))
    )
    (comp (ref "RF2")
      (value "15")
      (footprint "AXIAL-0.4-E24-0_25W-15-1%")
      (description "Resistor 15Ω 1/4W 1%")
      (fields
        (field (name "POWER") "1/4W")
        (field (name "TOLERANCE") "1%")
        (field (name "Comment") "Resistor 15 1/4W 1%")
      )
      (libsource (lib "Resistors") (part "Resistor 15 1/4W 1%"))
    )
    (comp (ref "RFB1")
      (value "36K")
      (footprint "AXIAL-0.4-E24-0_25W-36k-1%")
      (description "Resistor 36KΩ 1/4W 1%")
      (fields
        (field (name "POWER") "1/4W")
        (field (name "TOLERANCE") "1%")
        (field (name "Comment") "Resistor 36K 1/4W 1%")
      )
      (libsource (lib "Resistors") (part "Resistor 36K 1/4W 1%"))
    )
    (comp (ref "RFB2")
      (value "1.3k")
      (footprint "AXIAL-0.4-E24-0_25W-1.3k-1%")
      (description "Resistor 1.3kΩ 1/4W 1%")
      (fields
        (field (name "POWER") "1/4W")
        (field (name "TOLERANCE") "1%")
        (field (name "Comment") "Resistor 1.3k 1/4W 1%")
      )
      (libsource (lib "Resistors") (part "Resistor 1.3k 1/4W 1%"))
    )
    (comp (ref "RIOF")
      (value "36K")
      (footprint "AXIAL-0.4-E24-0_25W-36k-1%")
      (description "Resistor 36KΩ 1/4W 1%")
      (fields
        (field (name "POWER") "1/4W")
        (field (name "TYPE") "(TH) Metal film")
        (field (name "TOLERANCE") "1%")
        (field (name "Comment") "Resistor 36K 1/4W 1%")
      )
      (libsource (lib "Resistors") (part "Resistor 36K 1/4W 1%"))
    )
    (comp (ref "RL1")
      (value "20K")
      (footprint "AXIAL-0.6-E24-1W-20K")
      (description "Resistor 20KΩ 1W 5%")
      (fields
        (field (name "TOLERANCE") "5%")
        (field (name "POWER") "1W")
        (field (name "Comment") "Resistor 20K 1W 5%")
      )
      (libsource (lib "Resistors") (part "Resistor 20K 1W 5%"))
    )
    (comp (ref "RL2")
      (value "5.6K")
      (footprint "AXIAL-0.5-E24-0_5W-5.6K")
      (description "Resistor 5.6KΩ 1/2W 5%")
      (fields
        (field (name "TOLERANCE") "5%")
        (field (name "POWER") "1/2W")
        (field (name "Comment") "Resistor 5.6K 1/2W 5%")
      )
      (libsource (lib "Resistors") (part "Resistor 5.6K 1/2W 5%"))
    )
    (comp (ref "RMVM")
      (value "1.2k")
      (footprint "AXIAL-0.4-E24-0_25W-1.2k-1%")
      (description "Resistor 1.2kΩ 1/4W 1%")
      (fields
        (field (name "POWER") "1/4W")
        (field (name "TOLERANCE") "1%")
        (field (name "Comment") "Resistor 1.2k 1/4W 1%")
      )
      (libsource (lib "Resistors") (part "Resistor 1.2k 1/4W 1%"))
    )
    (comp (ref "RV1")
      (value "Trimmer Vertical 100 500mW 25-turn")
      (footprint "POT_3296W")
      (fields (field (name "TOLERANCE") "±10%") (field (name "ALTIUM_VALUE") "100"))
      (libsource (lib "Resistors") (part "RES_TRIMMER_100_25T_VERTICAL"))
    )
    (comp (ref "RV2")
      (value "Trimmer Vertical 100 500mW 25-turn")
      (footprint "POT_3296W")
      (fields (field (name "TOLERANCE") "±10%"))
      (libsource (lib "Resistors") (part "RES_TRIMMER_100_25T_VERTICAL"))
    )
    (comp (ref "RVC1")
      (value "Trimmer Vertical 2K 500mW 25-turn")
      (footprint "POT_3296W")
      (fields (field (name "TOLERANCE") "±10%"))
      (libsource (lib "Resistors") (part "RES_TRIMMER_2K_25T_VERTICAL"))
    )
    (comp (ref "RVC2")
      (value "Trimmer Vertical 2K 500mW 25-turn")
      (footprint "POT_3296W")
      (fields (field (name "TOLERANCE") "±10%"))
      (libsource (lib "Resistors") (part "RES_TRIMMER_2K_25T_VERTICAL"))
    )
    (comp (ref "RVMV")
      (value "Trimmer Vertical 1K 500mW 25-turn")
      (footprint "POT_3296W")
      (fields (field (name "TOLERANCE") "±10%"))
      (libsource (lib "Resistors") (part "RES_TRIMMER_1K_25T_VERTICAL"))
    )
    (comp (ref "TP+HV")
      (value "TESTPOINT_THT")
      (footprint "TP-THT-MULTI")
      (description "Test Point PCB mount Multi-purpose Black")
      (fields (field (name "PBL PART NUMBER") "3100-xxx"))
      (libsource (lib "Test Points and Jumpers") (part "TESTPOINT_THT"))
    )
    (comp (ref "TP+LV")
      (value "TESTPOINT_THT")
      (footprint "TP-THT-MULTI")
      (description "Test Point PCB mount Multi-purpose Black")
      (fields (field (name "PBL PART NUMBER") "3100-xxx"))
      (libsource (lib "Test Points and Jumpers") (part "TESTPOINT_THT"))
    )
    (comp (ref "TP+RLV")
      (value "TESTPOINT_THT")
      (footprint "TP-THT-MULTI")
      (description "Test Point PCB mount Multi-purpose Black")
      (fields (field (name "PBL PART NUMBER") "3100-xxx"))
      (libsource (lib "Test Points and Jumpers") (part "TESTPOINT_THT"))
    )
    (comp (ref "TP-HV")
      (value "TESTPOINT_THT")
      (footprint "TP-THT-MULTI")
      (description "Test Point PCB mount Multi-purpose Black")
      (fields (field (name "PBL PART NUMBER") "3100-xxx"))
      (libsource (lib "Test Points and Jumpers") (part "TESTPOINT_THT"))
    )
    (comp (ref "TP-LV")
      (value "TESTPOINT_THT")
      (footprint "TP-THT-MULTI")
      (description "Test Point PCB mount Multi-purpose Black")
      (fields (field (name "PBL PART NUMBER") "3100-xxx"))
      (libsource (lib "Test Points and Jumpers") (part "TESTPOINT_THT"))
    )
    (comp (ref "TP-RLV")
      (value "TESTPOINT_THT")
      (footprint "TP-THT-MULTI")
      (description "Test Point PCB mount Multi-purpose Black")
      (fields (field (name "PBL PART NUMBER") "3100-xxx"))
      (libsource (lib "Test Points and Jumpers") (part "TESTPOINT_THT"))
    )
    (comp (ref "TP1")
      (value "TESTPOINT_THT")
      (footprint "TP-THT-MULTI")
      (description "Test Point PCB mount Multi-purpose Black")
      (fields (field (name "PBL PART NUMBER") "3100-xxx"))
      (libsource (lib "Test Points and Jumpers") (part "TESTPOINT_THT"))
    )
    (comp (ref "TP2")
      (value "TESTPOINT_THT")
      (footprint "TP-THT-MULTI")
      (description "Test Point PCB mount Multi-purpose Black")
      (fields (field (name "PBL PART NUMBER") "3100-xxx"))
      (libsource (lib "Test Points and Jumpers") (part "TESTPOINT_THT"))
    )
    (comp (ref "TP3")
      (value "TESTPOINT_THT")
      (footprint "TP-THT-MULTI")
      (description "Test Point PCB mount Multi-purpose Black")
      (fields (field (name "PBL PART NUMBER") "3100-xxx"))
      (libsource (lib "Test Points and Jumpers") (part "TESTPOINT_THT"))
    )
    (comp (ref "TP4")
      (value "TESTPOINT_THT")
      (footprint "TP-THT-MULTI")
      (description "Test Point PCB mount Multi-purpose Black")
      (fields (field (name "PBL PART NUMBER") "3100-xxx"))
      (libsource (lib "Test Points and Jumpers") (part "TESTPOINT_THT"))
    )
    (comp (ref "TP5")
      (value "TESTPOINT_THT")
      (footprint "TP-THT-MULTI")
      (description "Test Point PCB mount Multi-purpose Black")
      (fields (field (name "PBL PART NUMBER") "3100-xxx"))
      (libsource (lib "Test Points and Jumpers") (part "TESTPOINT_THT"))
    )
    (comp (ref "TP6")
      (value "TESTPOINT_THT")
      (footprint "TP-THT-MULTI")
      (description "Test Point PCB mount Multi-purpose Black")
      (fields (field (name "PBL PART NUMBER") "3100-xxx"))
      (libsource (lib "Test Points and Jumpers") (part "TESTPOINT_THT"))
    )
    (comp (ref "TP7")
      (value "TESTPOINT_THT")
      (footprint "TP-THT-MULTI")
      (description "Test Point PCB mount Multi-purpose Black")
      (fields (field (name "PBL PART NUMBER") "3100-xxx"))
      (libsource (lib "Test Points and Jumpers") (part "TESTPOINT_THT"))
    )
    (comp (ref "TP8")
      (value "TESTPOINT_THT")
      (footprint "TP-THT-MULTI")
      (description "Test Point PCB mount Multi-purpose Black")
      (fields (field (name "PBL PART NUMBER") "3100-xxx"))
      (libsource (lib "Test Points and Jumpers") (part "TESTPOINT_THT"))
    )
    (comp (ref "TP9")
      (value "TESTPOINT_THT")
      (footprint "TP-THT-MULTI")
      (description "Test Point PCB mount Multi-purpose Black")
      (fields (field (name "PBL PART NUMBER") "3100-xxx"))
      (libsource (lib "Test Points and Jumpers") (part "TESTPOINT_THT"))
    )
    (comp (ref "TP10")
      (value "TESTPOINT_THT")
      (footprint "TP-THT-MULTI")
      (description "Test Point PCB mount Multi-purpose Black")
      (fields (field (name "PBL PART NUMBER") "3100-xxx"))
      (libsource (lib "Test Points and Jumpers") (part "TESTPOINT_THT"))
    )
    (comp (ref "TP11")
      (value "TESTPOINT_THT")
      (footprint "TP-THT-MULTI")
      (description "Test Point PCB mount Multi-purpose Black")
      (fields (field (name "PBL PART NUMBER") "3100-xxx"))
      (libsource (lib "Test Points and Jumpers") (part "TESTPOINT_THT"))
    )
    (comp (ref "TP12")
      (value "TESTPOINT_THT")
      (footprint "TP-THT-MULTI")
      (description "Test Point PCB mount Multi-purpose Black")
      (fields (field (name "PBL PART NUMBER") "3100-xxx"))
      (libsource (lib "Test Points and Jumpers") (part "TESTPOINT_THT"))
    )
    (comp (ref "TPGND")
      (value "TESTPOINT_THT")
      (footprint "TP-THT-MULTI")
      (description "Test Point PCB mount Multi-purpose Black")
      (fields (field (name "PBL PART NUMBER") "3100-xxx"))
      (libsource (lib "Test Points and Jumpers") (part "TESTPOINT_THT"))
    )
    (comp (ref "TPIN")
      (value "TESTPOINT_THT")
      (footprint "TP-THT-MULTI")
      (description "Test Point PCB mount Multi-purpose Black")
      (fields (field (name "PBL PART NUMBER") "3100-xxx"))
      (libsource (lib "Test Points and Jumpers") (part "TESTPOINT_THT"))
    )
    (comp (ref "TPMIDMV")
      (value "Pin")
      (footprint "Jumper 200mil 1 pin")
      (description "Jumper Wire")
      (fields (field (name "PUBLISHER") "Altium Limited"))
      (libsource (lib "Test Points and Jumpers") (part "Pin"))
    )
    (comp (ref "TPOUT")
      (value "TESTPOINT_THT")
      (footprint "TP-THT-MULTI")
      (description "Test Point PCB mount Multi-purpose Black")
      (fields (field (name "PBL PART NUMBER") "3100-xxx"))
      (libsource (lib "Test Points and Jumpers") (part "TESTPOINT_THT"))
    )
  )
  (nets
    (net (code "1") (name "+HV") (class "Default")
      (node (ref "B1") (pin "1") (pinfunction "1_1") (pintype "power_in"))
      (node (ref "CC3") (pin "2") (pinfunction "2_2") (pintype "passive"))
      (node (ref "CF1") (pin "1") (pinfunction "1_1") (pintype "passive"))
      (node (ref "CF5") (pin "2") (pinfunction "2_2") (pintype "passive"))
      (node (ref "LED1") (pin "A") (pinfunction "A_A") (pintype "passive"))
      (node (ref "Q1") (pin "2") (pinfunction "C_2") (pintype "passive"))
      (node (ref "Q5") (pin "2") (pinfunction "C_2") (pintype "passive"))
      (node (ref "Q7") (pin "2") (pinfunction "C_2") (pintype "passive"))
      (node (ref "Q9") (pin "2") (pinfunction "C_2") (pintype "passive"))
      (node (ref "RF1") (pin "2") (pinfunction "2_2") (pintype "passive"))
      (node (ref "TP+HV") (pin "1") (pintype "passive"))
    )
    (net (code "2") (name "+LV") (class "Default")
      (node (ref "B3") (pin "1") (pinfunction "1_1") (pintype "power_in"))
      (node (ref "CF3") (pin "1") (pinfunction "1_1") (pintype "passive"))
      (node (ref "CF35") (pin "1") (pinfunction "1_1") (pintype "passive"))
      (node (ref "CF37") (pin "2") (pinfunction "2_2") (pintype "passive"))
      (node (ref "CF7") (pin "2") (pinfunction "2_2") (pintype "passive"))
      (node (ref "D1") (pin "3") (pinfunction "A_3") (pintype "passive"))
      (node (ref "IC1") (pin "3") (pinfunction "INPUT_3") (pintype "input"))
      (node (ref "LED2") (pin "A") (pinfunction "A_A") (pintype "passive"))
      (node (ref "TP+LV") (pin "1") (pintype "passive"))
    )
    (net (code "3") (name "+RLV") (class "Default")
      (node (ref "CF31") (pin "1") (pinfunction "1_1") (pintype "passive"))
      (node (ref "CF33") (pin "2") (pinfunction "2_2") (pintype "passive"))
      (node (ref "CF39") (pin "1") (pinfunction "1_1") (pintype "passive"))
      (node (ref "D38") (pin "2") (pinfunction "A_2") (pintype "passive"))
      (node (ref "IC1") (pin "1") (pinfunction "OUTPUT_1") (pintype "output"))
      (node (ref "Q31") (pin "1") (pinfunction "B_1") (pintype "passive"))
      (node (ref "Q37") (pin "1") (pinfunction "B_1") (pintype "passive"))
      (node (ref "R34") (pin "1") (pintype "passive"))
      (node (ref "TP+RLV") (pin "1") (pintype "passive"))
      (node (ref "TP12") (pin "1") (pintype "passive"))
    )
    (net (code "4") (name "-HV") (class "Default")
      (node (ref "B2") (pin "1") (pinfunction "1_1") (pintype "power_in"))
      (node (ref "CC4") (pin "1") (pinfunction "1_1") (pintype "passive"))
      (node (ref "CF2") (pin "2") (pinfunction "2_2") (pintype "passive"))
      (node (ref "CF6") (pin "1") (pinfunction "1_1") (pintype "passive"))
      (node (ref "Q10") (pin "2") (pinfunction "C_2") (pintype "passive"))
      (node (ref "Q2") (pin "3") (pinfunction "E_3") (pintype "passive"))
      (node (ref "Q6") (pin "3") (pinfunction "E_3") (pintype "passive"))
      (node (ref "Q8") (pin "2") (pinfunction "C_2") (pintype "passive"))
      (node (ref "RF2") (pin "2") (pinfunction "2_2") (pintype "passive"))
      (node (ref "RL1") (pin "1") (pinfunction "1_1") (pintype "passive"))
      (node (ref "TP-HV") (pin "1") (pintype "passive"))
    )
    (net (code "5") (name "-LV") (class "Default")
      (node (ref "B4") (pin "1") (pinfunction "1_1") (pintype "power_in"))
      (node (ref "CF36") (pin "2") (pinfunction "2_2") (pintype "passive"))
      (node (ref "CF38") (pin "1") (pinfunction "1_1") (pintype "passive"))
      (node (ref "CF4") (pin "2") (pinfunction "2_2") (pintype "passive"))
      (node (ref "CF8") (pin "1") (pinfunction "1_1") (pintype "passive"))
      (node (ref "D2") (pin "1") (pinfunction "K_1") (pintype "passive"))
      (node (ref "IC2") (pin "2") (pinfunction "INPUT_2") (pintype "input"))
      (node (ref "RL2") (pin "1") (pinfunction "1_1") (pintype "passive"))
      (node (ref "TP-LV") (pin "1") (pintype "passive"))
    )
    (net (code "6") (name "-RLV") (class "Default")
      (node (ref "CCF32") (pin "2") (pinfunction "2_2") (pintype "passive"))
      (node (ref "CF34") (pin "2") (pinfunction "2_2") (pintype "passive"))
      (node (ref "CF40") (pin "2") (pinfunction "2_2") (pintype "passive"))
      (node (ref "D37") (pin "1") (pinfunction "K_1") (pintype "passive"))
      (node (ref "IC2") (pin "3") (pinfunction "OUTPUT_3") (pintype "output"))
      (node (ref "Q32") (pin "1") (pinfunction "B_1") (pintype "passive"))
      (node (ref "Q38") (pin "1") (pinfunction "B_1") (pintype "passive"))
      (node (ref "R33") (pin "1") (pintype "passive"))
      (node (ref "TP-RLV") (pin "1") (pintype "passive"))
      (node (ref "TP11") (pin "1") (pintype "passive"))
    )
    (net (code "7") (name "/+HVF") (class "Default")
      (node (ref "CF11") (pin "2") (pinfunction "2_2") (pintype "passive"))
      (node (ref "CF9") (pin "1") (pinfunction "1_1") (pintype "passive"))
      (node (ref "R15") (pin "2") (pinfunction "2_2") (pintype "passive"))
      (node (ref "R19") (pin "2") (pinfunction "2_2") (pintype "passive"))
      (node (ref "R31") (pin "2") (pinfunction "2_2") (pintype "passive"))
      (node (ref "R35") (pin "2") (pinfunction "2_2") (pintype "passive"))
      (node (ref "RF1") (pin "1") (pinfunction "1_1") (pintype "passive"))
      (node (ref "TP5") (pin "1") (pintype "passive"))
    )
    (net (code "8") (name "/-HVF") (class "Default")
      (node (ref "CF10") (pin "2") (pinfunction "2_2") (pintype "passive"))
      (node (ref "CF12") (pin "2") (pinfunction "2_2") (pintype "passive"))
      (node (ref "R16") (pin "2") (pinfunction "2_2") (pintype "passive"))
      (node (ref "R32") (pin "2") (pinfunction "2_2") (pintype "passive"))
      (node (ref "R36") (pin "2") (pinfunction "2_2") (pintype "passive"))
      (node (ref "RF2") (pin "1") (pinfunction "1_1") (pintype "passive"))
      (node (ref "TP6") (pin "1") (pintype "passive"))
    )
    (net (code "9") (name "/HOutNet0") (class "Default")
      (node (ref "BO") (pin "1") (pinfunction "1_1") (pintype "passive"))
      (node (ref "JU5") (pin "2") (pinfunction "C2_2") (pintype "passive"))
      (node (ref "Q11") (pin "1") (pinfunction "E_1") (pintype "passive"))
      (node (ref "Q12") (pin "1") (pinfunction "E_1") (pintype "passive"))
      (node (ref "R3") (pin "2") (pinfunction "2_2") (pintype "passive"))
      (node (ref "R4") (pin "1") (pinfunction "1_1") (pintype "passive"))
      (node (ref "TPOUT") (pin "1") (pintype "passive"))
    )
    (net (code "10") (name "/HOutNet1") (class "Default")
      (node (ref "Q3") (pin "3") (pinfunction "E_3") (pintype "passive"))
      (node (ref "R3") (pin "1") (pinfunction "1_1") (pintype "passive"))
      (node (ref "R7") (pin "2") (pinfunction "2_2") (pintype "passive"))
      (node (ref "TP1") (pin "1") (pintype "passive"))
    )
    (net (code "11") (name "/HOutNet2") (class "Default")
      (node (ref "Q4") (pin "2") (pinfunction "C_2") (pintype "passive"))
      (node (ref "R4") (pin "2") (pinfunction "2_2") (pintype "passive"))
      (node (ref "R8") (pin "1") (pinfunction "1_1") (pintype "passive"))
      (node (ref "TP2") (pin "1") (pintype "passive"))
    )
    (net (code "12") (name "/H{slash}2OutNet1") (class "Default")
      (node (ref "Q1") (pin "3") (pinfunction "E_3") (pintype "passive"))
      (node (ref "R1") (pin "2") (pinfunction "2_2") (pintype "passive"))
    )
    (net (code "13") (name "/H{slash}2OutNet2") (class "Default")
      (node (ref "Q2") (pin "2") (pinfunction "C_2") (pintype "passive"))
      (node (ref "R2") (pin "1") (pinfunction "1_1") (pintype "passive"))
    )
    (net (code "14") (name "/H{slash}2OutNet3") (class "Default")
      (node (ref "D1") (pin "1") (pinfunction "K_1") (pintype "passive"))
      (node (ref "Q3") (pin "2") (pinfunction "C_2") (pintype "passive"))
      (node (ref "R1") (pin "1") (pinfunction "1_1") (pintype "passive"))
      (node (ref "R13") (pin "2") (pinfunction "2_2") (pintype "passive"))
      (node (ref "R5") (pin "1") (pinfunction "1_1") (pintype "passive"))
      (node (ref "R9") (pin "1") (pinfunction "1_1") (pintype "passive"))
    )
    (net (code "15") (name "/H{slash}2OutNet4") (class "Default")
      (node (ref "D2") (pin "3") (pinfunction "A_3") (pintype "passive"))
      (node (ref "Q4") (pin "3") (pinfunction "E_3") (pintype "passive"))
      (node (ref "R10") (pin "2") (pinfunction "2_2") (pintype "passive"))
      (node (ref "R14") (pin "1") (pinfunction "1_1") (pintype "passive"))
      (node (ref "R2") (pin "2") (pinfunction "2_2") (pintype "passive"))
      (node (ref "R6") (pin "2") (pinfunction "2_2") (pintype "passive"))
    )
    (net (code "16") (name "/H{slash}2OutNet5") (class "Default")
      (node (ref "Q5") (pin "3") (pinfunction "E_3") (pintype "passive"))
      (node (ref "R5") (pin "2") (pinfunction "2_2") (pintype "passive"))
    )
    (net (code "17") (name "/H{slash}2OutNet6") (class "Default")
      (node (ref "Q6") (pin "2") (pinfunction "C_2") (pintype "passive"))
      (node (ref "R6") (pin "1") (pinfunction "1_1") (pintype "passive"))
    )
    (net (code "18") (name "/NEG_DIFF_OUT") (class "Default")
      (node (ref "CC6") (pin "2") (pinfunction "2_2") (pintype "passive"))
      (node (ref "Q18") (pin "2") (pinfunction "B_2") (pintype "passive"))
      (node (ref "Q38") (pin "3") (pinfunction "C_3") (pintype "passive"))
      (node (ref "RVC2") (pin "1") (pinfunction "A_1") (pintype "passive"))
      (node (ref "RVC2") (pin "2") (pinfunction "B_2") (pintype "passive"))
      (node (ref "TP8") (pin "1") (pintype "passive"))
    )
    (net (code "19") (name "/POS_DIFF_OUT") (class "Default")
      (node (ref "CC5") (pin "1") (pinfunction "1_1") (pintype "passive"))
      (node (ref "Q17") (pin "2") (pinfunction "B_2") (pintype "passive"))
      (node (ref "Q37") (pin "3") (pinfunction "C_3") (pintype "passive"))
      (node (ref "RVC1") (pin "1") (pinfunction "A_1") (pintype "passive"))
      (node (ref "RVC1") (pin "2") (pinfunction "B_2") (pintype "passive"))
      (node (ref "TP7") (pin "1") (pintype "passive"))
    )
    (net (code "20") (name "/VBM1") (class "Default")
      (node (ref "CC2") (pin "2") (pinfunction "2_2") (pintype "passive"))
      (node (ref "DZ1") (pin "1") (pinfunction "A_1") (pintype "passive"))
      (node (ref "JU3") (pin "1") (pinfunction "C1_1") (pintype "passive"))
      (node (ref "Q19") (pin "2") (pinfunction "C_2") (pintype "passive"))
      (node (ref "R21") (pin "2") (pinfunction "2_2") (pintype "passive"))
    )
    (net (code "21") (name "/VBM2") (class "Default")
      (node (ref "CC2") (pin "1") (pinfunction "1_1") (pintype "passive"))
      (node (ref "DZ2") (pin "2") (pinfunction "K_2") (pintype "passive"))
      (node (ref "JU4") (pin "1") (pinfunction "C1_1") (pintype "passive"))
      (node (ref "Q20") (pin "2") (pinfunction "C_2") (pintype "passive"))
      (node (ref "R22") (pin "1") (pinfunction "1_1") (pintype "passive"))
    )
    (net (code "22") (name "GND") (class "Default")
      (node (ref "B1") (pin "2") (pinfunction "2_2") (pintype "passive"))
      (node (ref "B2") (pin "2") (pinfunction "2_2") (pintype "passive"))
      (node (ref "B3") (pin "2") (pinfunction "2_2") (pintype "passive"))
      (node (ref "B4") (pin "2") (pinfunction "2_2") (pintype "passive"))
      (node (ref "BO") (pin "2") (pinfunction "2_2") (pintype "passive"))
      (node (ref "CAF") (pin "1") (pinfunction "1_1") (pintype "passive"))
      (node (ref "CCF32") (pin "1") (pinfunction "1_1") (pintype "passive"))
      (node (ref "CF1") (pin "2") (pinfunction "2_2") (pintype "passive"))
      (node (ref "CF10") (pin "1") (pinfunction "1_1") (pintype "passive"))
      (node (ref "CF11") (pin "1") (pinfunction "1_1") (pintype "passive"))
      (node (ref "CF12") (pin "1") (pinfunction "1_1") (pintype "passive"))
      (node (ref "CF2") (pin "1") (pinfunction "1_1") (pintype "passive"))
      (node (ref "CF3") (pin "2") (pinfunction "2_2") (pintype "passive"))
      (node (ref "CF31") (pin "2") (pinfunction "2_2") (pintype "passive"))
      (node (ref "CF33") (pin "1") (pinfunction "1_1") (pintype "passive"))
      (node (ref "CF34") (pin "1") (pinfunction "1_1") (pintype "passive"))
      (node (ref "CF35") (pin "2") (pinfunction "2_2") (pintype "passive"))
      (node (ref "CF36") (pin "1") (pinfunction "1_1") (pintype "passive"))
      (node (ref "CF37") (pin "1") (pinfunction "1_1") (pintype "passive"))
      (node (ref "CF38") (pin "2") (pinfunction "2_2") (pintype "passive"))
      (node (ref "CF39") (pin "2") (pinfunction "2_2") (pintype "passive"))
      (node (ref "CF4") (pin "1") (pinfunction "1_1") (pintype "passive"))
      (node (ref "CF40") (pin "1") (pinfunction "1_1") (pintype "passive"))
      (node (ref "CF5") (pin "1") (pinfunction "1_1") (pintype "passive"))
      (node (ref "CF6") (pin "2") (pinfunction "2_2") (pintype "passive"))
      (node (ref "CF7") (pin "1") (pinfunction "1_1") (pintype "passive"))
      (node (ref "CF8") (pin "2") (pinfunction "2_2") (pintype "passive"))
      (node (ref "CF9") (pin "2") (pinfunction "2_2") (pintype "passive"))
      (node (ref "D32") (pin "2") (pinfunction "A_2") (pintype "passive"))
      (node (ref "D34") (pin "1") (pinfunction "K_1") (pintype "passive"))
      (node (ref "IC1") (pin "2") (pinfunction "GND_2") (pintype "passive"))
      (node (ref "IC2") (pin "1") (pinfunction "GND_1") (pintype "passive"))
      (node (ref "JI") (pin "1") (pinfunction "1_1") (pintype "passive"))
      (node (ref "JI") (pin "2") (pinfunction "2_2") (pintype "passive"))
      (node (ref "JU1") (pin "3") (pinfunction "C3_3") (pintype "passive"))
      (node (ref "JU2") (pin "3") (pinfunction "C3_3") (pintype "passive"))
      (node (ref "JU3") (pin "3") (pinfunction "C3_3") (pintype "passive"))
      (node (ref "JU4") (pin "3") (pinfunction "C3_3") (pintype "passive"))
      (node (ref "Q17") (pin "3") (pinfunction "C_3") (pintype "passive"))
      (node (ref "Q18") (pin "3") (pinfunction "C_3") (pintype "passive"))
      (node (ref "R37") (pin "2") (pintype "passive"))
      (node (ref "R38") (pin "2") (pintype "passive"))
      (node (ref "RIOF") (pin "2") (pinfunction "2_2") (pintype "passive"))
      (node (ref "TPGND") (pin "1") (pintype "passive"))
    )
    (net (code "23") (name "Net-(CAI-Pad1)") (class "Default")
      (node (ref "CAI") (pin "1") (pinfunction "1_1") (pintype "passive"))
      (node (ref "JI") (pin "3") (pinfunction "3_3") (pintype "passive"))
      (node (ref "TPIN") (pin "1") (pintype "passive"))
    )
    (net (code "24") (name "Net-(D3-A)") (class "Default")
      (node (ref "D3") (pin "2") (pinfunction "A_2") (pintype "passive"))
      (node (ref "JU1") (pin "2") (pinfunction "C2_2") (pintype "passive"))
    )
    (net (code "25") (name "Net-(D3-K)") (class "Default")
      (node (ref "CC3") (pin "1") (pinfunction "1_1") (pintype "passive"))
      (node (ref "D3") (pin "1") (pinfunction "K_1") (pintype "passive"))
      (node (ref "Q7") (pin "3") (pinfunction "B_3") (pintype "passive"))
    )
    (net (code "26") (name "Net-(D4-A)") (class "Default")
      (node (ref "CC4") (pin "2") (pinfunction "2_2") (pintype "passive"))
      (node (ref "D4") (pin "2") (pinfunction "A_2") (pintype "passive"))
      (node (ref "Q8") (pin "3") (pinfunction "B_3") (pintype "passive"))
    )
    (net (code "27") (name "Net-(D4-K)") (class "Default")
      (node (ref "D4") (pin "1") (pinfunction "K_1") (pintype "passive"))
      (node (ref "JU2") (pin "2") (pinfunction "C2_2") (pintype "passive"))
    )
    (net (code "28") (name "Net-(D5-A)") (class "Default")
      (node (ref "D5") (pin "2") (pinfunction "A_2") (pintype "passive"))
      (node (ref "Q9") (pin "3") (pinfunction "B_3") (pintype "passive"))
      (node (ref "R17") (pin "2") (pinfunction "2_2") (pintype "passive"))
    )
    (net (code "29") (name "Net-(D5-K)") (class "Default")
      (node (ref "D5") (pin "1") (pinfunction "K_1") (pintype "passive"))
      (node (ref "Q11") (pin "3") (pinfunction "C_3") (pintype "passive"))
    )
    (net (code "30") (name "Net-(D6-A)") (class "Default")
      (node (ref "D6") (pin "2") (pinfunction "A_2") (pintype "passive"))
      (node (ref "Q12") (pin "3") (pinfunction "C_3") (pintype "passive"))
    )
    (net (code "31") (name "Net-(D6-K)") (class "Default")
      (node (ref "D6") (pin "1") (pinfunction "K_1") (pintype "passive"))
      (node (ref "Q10") (pin "3") (pinfunction "B_3") (pintype "passive"))
      (node (ref "R18") (pin "1") (pinfunction "1_1") (pintype "passive"))
    )
    (net (code "32") (name "Net-(D31-A)") (class "Default")
      (node (ref "D31") (pin "2") (pinfunction "A_2") (pintype "passive"))
      (node (ref "D32") (pin "1") (pinfunction "K_1") (pintype "passive"))
    )
    (net (code "33") (name "Net-(D31-K)") (class "Default")
      (node (ref "CAF") (pin "2") (pinfunction "2_2") (pintype "passive"))
      (node (ref "D31") (pin "1") (pinfunction "K_1") (pintype "passive"))
      (node (ref "D33") (pin "2") (pinfunction "A_2") (pintype "passive"))
      (node (ref "RFB2") (pin "1") (pinfunction "1_1") (pintype "passive"))
    )
    (net (code "34") (name "Net-(D33-K)") (class "Default")
      (node (ref "D33") (pin "1") (pinfunction "K_1") (pintype "passive"))
      (node (ref "D34") (pin "2") (pinfunction "A_2") (pintype "passive"))
    )
    (net (code "35") (name "Net-(D35-A)") (class "Default")
      (node (ref "D35") (pin "2") (pinfunction "A_2") (pintype "passive"))
      (node (ref "Q35") (pin "1") (pinfunction "B_1") (pintype "passive"))
      (node (ref "R37") (pin "1") (pintype "passive"))
    )
    (net (code "36") (name "Net-(D35-K)") (class "Default")
      (node (ref "D35") (pin "1") (pinfunction "K_1") (pintype "passive"))
      (node (ref "D37") (pin "2") (pinfunction "A_2") (pintype "passive"))
    )
    (net (code "37") (name "Net-(D36-A)") (class "Default")
      (node (ref "D36") (pin "2") (pinfunction "A_2") (pintype "passive"))
      (node (ref "D38") (pin "1") (pinfunction "K_1") (pintype "passive"))
    )
    (net (code "38") (name "Net-(D36-K)") (class "Default")
      (node (ref "D36") (pin "1") (pinfunction "K_1") (pintype "passive"))
      (node (ref "R38") (pin "1") (pintype "passive"))
    )
    (net (code "39") (name "Net-(DZ1-K)") (class "Default")
      (node (ref "CC5") (pin "2") (pinfunction "2_2") (pintype "passive"))
      (node (ref "DZ1") (pin "2") (pinfunction "K_2") (pintype "passive"))
      (node (ref "JU1") (pin "1") (pinfunction "C1_1") (pintype "passive"))
      (node (ref "Q15") (pin "1") (pinfunction "E_1") (pintype "passive"))
    )
    (net (code "40") (name "Net-(DZ2-A)") (class "Default")
      (node (ref "CC6") (pin "1") (pinfunction "1_1") (pintype "passive"))
      (node (ref "DZ2") (pin "1") (pinfunction "A_1") (pintype "passive"))
      (node (ref "JU2") (pin "1") (pinfunction "C1_1") (pintype "passive"))
      (node (ref "Q16") (pin "2") (pinfunction "C_2") (pintype "passive"))
    )
    (net (code "41") (name "Net-(DZ3-A)") (class "Default")
      (node (ref "DZ3") (pin "1") (pinfunction "A_1") (pintype "passive"))
      (node (ref "Q17") (pin "1") (pinfunction "E_1") (pintype "passive"))
    )
    (net (code "42") (name "Net-(DZ3-K)") (class "Default")
      (node (ref "DZ3") (pin "2") (pinfunction "K_2") (pintype "passive"))
      (node (ref "Q15") (pin "3") (pinfunction "B_3") (pintype "passive"))
      (node (ref "R19") (pin "1") (pinfunction "1_1") (pintype "passive"))
    )
    (net (code "43") (name "Net-(DZ4-A)") (class "Default")
      (node (ref "DZ4") (pin "1") (pinfunction "A_1") (pintype "passive"))
      (node (ref "Q16") (pin "3") (pinfunction "B_3") (pintype "passive"))
      (node (ref "R20") (pin "2") (pinfunction "2_2") (pintype "passive"))
    )
    (net (code "44") (name "Net-(DZ4-K)") (class "Default")
      (node (ref "DZ4") (pin "2") (pinfunction "K_2") (pintype "passive"))
      (node (ref "Q18") (pin "1") (pinfunction "E_1") (pintype "passive"))
    )
    (net (code "45") (name "Net-(JU3-C2)") (class "Default")
      (node (ref "JU3") (pin "2") (pinfunction "C2_2") (pintype "passive"))
      (node (ref "R17") (pin "1") (pinfunction "1_1") (pintype "passive"))
    )
    (net (code "46") (name "Net-(JU4-C2)") (class "Default")
      (node (ref "JU4") (pin "2") (pinfunction "C2_2") (pintype "passive"))
      (node (ref "R18") (pin "2") (pinfunction "2_2") (pintype "passive"))
    )
    (net (code "47") (name "Net-(JU5-C1)") (class "Default")
      (node (ref "CC7") (pin "2") (pinfunction "2_2") (pintype "passive"))
      (node (ref "JU5") (pin "1") (pinfunction "C1_1") (pintype "passive"))
      (node (ref "RFB1") (pin "2") (pinfunction "2_2") (pintype "passive"))
    )
    (net (code "48") (name "Net-(LED1-PadK)") (class "Default")
      (node (ref "LED1") (pin "K") (pinfunction "K_K") (pintype "passive"))
      (node (ref "RL1") (pin "2") (pinfunction "2_2") (pintype "passive"))
    )
    (net (code "49") (name "Net-(LED2-PadK)") (class "Default")
      (node (ref "LED2") (pin "K") (pinfunction "K_K") (pintype "passive"))
      (node (ref "RL2") (pin "2") (pinfunction "2_2") (pintype "passive"))
    )
    (net (code "50") (name "Net-(Q1-B)") (class "Default")
      (node (ref "Q1") (pin "1") (pinfunction "B_1") (pintype "passive"))
      (node (ref "Q5") (pin "1") (pinfunction "B_1") (pintype "passive"))
      (node (ref "Q7") (pin "1") (pinfunction "E_1") (pintype "passive"))
      (node (ref "R9") (pin "2") (pinfunction "2_2") (pintype "passive"))
    )
    (net (code "51") (name "Net-(Q2-B)") (class "Default")
      (node (ref "Q2") (pin "1") (pinfunction "B_1") (pintype "passive"))
      (node (ref "Q6") (pin "1") (pinfunction "B_1") (pintype "passive"))
      (node (ref "Q8") (pin "1") (pinfunction "E_1") (pintype "passive"))
      (node (ref "R10") (pin "1") (pinfunction "1_1") (pintype "passive"))
    )
    (net (code "52") (name "Net-(Q3-B)") (class "Default")
      (node (ref "CC1") (pin "2") (pinfunction "2_2") (pintype "passive"))
      (node (ref "Q3") (pin "1") (pinfunction "B_1") (pintype "passive"))
      (node (ref "Q9") (pin "1") (pinfunction "E_1") (pintype "passive"))
      (node (ref "R11") (pin "2") (pinfunction "2_2") (pintype "passive"))
    )
    (net (code "53") (name "Net-(Q10-E)") (class "Default")
      (node (ref "CC1") (pin "1") (pinfunction "1_1") (pintype "passive"))
      (node (ref "Q10") (pin "1") (pinfunction "E_1") (pintype "passive"))
      (node (ref "Q4") (pin "1") (pinfunction "B_1") (pintype "passive"))
      (node (ref "R12") (pin "1") (pinfunction "1_1") (pintype "passive"))
    )
    (net (code "54") (name "Net-(Q11-B)") (class "Default")
      (node (ref "Q11") (pin "2") (pinfunction "B_2") (pintype "passive"))
      (node (ref "R13") (pin "1") (pinfunction "1_1") (pintype "passive"))
      (node (ref "R7") (pin "1") (pinfunction "1_1") (pintype "passive"))
    )
    (net (code "55") (name "Net-(Q12-B)") (class "Default")
      (node (ref "Q12") (pin "2") (pinfunction "B_2") (pintype "passive"))
      (node (ref "R14") (pin "2") (pinfunction "2_2") (pintype "passive"))
      (node (ref "R8") (pin "2") (pinfunction "2_2") (pintype "passive"))
    )
    (net (code "56") (name "Net-(Q15-C)") (class "Default")
      (node (ref "Q15") (pin "2") (pinfunction "C_2") (pintype "passive"))
      (node (ref "R15") (pin "1") (pinfunction "1_1") (pintype "passive"))
      (node (ref "TP3") (pin "1") (pintype "passive"))
    )
    (net (code "57") (name "Net-(Q16-E)") (class "Default")
      (node (ref "Q16") (pin "1") (pinfunction "E_1") (pintype "passive"))
      (node (ref "R16") (pin "1") (pinfunction "1_1") (pintype "passive"))
      (node (ref "TP4") (pin "1") (pintype "passive"))
    )
    (net (code "58") (name "Net-(Q19-B)") (class "Default")
      (node (ref "Q19") (pin "3") (pinfunction "B_3") (pintype "passive"))
      (node (ref "R21") (pin "1") (pinfunction "1_1") (pintype "passive"))
      (node (ref "RVMV") (pin "1") (pinfunction "A_1") (pintype "passive"))
    )
    (net (code "59") (name "Net-(Q19-E)") (class "Default")
      (node (ref "Q19") (pin "1") (pinfunction "E_1") (pintype "passive"))
      (node (ref "Q20") (pin "1") (pinfunction "E_1") (pintype "passive"))
      (node (ref "TPMIDMV") (pin "1") (pinfunction "C1_1") (pintype "passive"))
    )
    (net (code "60") (name "Net-(Q20-B)") (class "Default")
      (node (ref "Q20") (pin "3") (pinfunction "B_3") (pintype "passive"))
      (node (ref "R22") (pin "2") (pinfunction "2_2") (pintype "passive"))
      (node (ref "RMVM") (pin "1") (pinfunction "1_1") (pintype "passive"))
    )
    (net (code "61") (name "Net-(Q31-C)") (class "Default")
      (node (ref "Q31") (pin "3") (pinfunction "C_3") (pintype "passive"))
      (node (ref "R31") (pin "1") (pinfunction "1_1") (pintype "passive"))
    )
    (net (code "62") (name "Net-(Q31-E)") (class "Default")
      (node (ref "Q31") (pin "2") (pinfunction "E_2") (pintype "passive"))
      (node (ref "QI") (pin "3") (pinfunction "C2_3") (pintype "passive"))
      (node (ref "QI") (pin "4") (pinfunction "C2_4") (pintype "passive"))
    )
    (net (code "63") (name "Net-(Q32-C)") (class "Default")
      (node (ref "Q32") (pin "3") (pinfunction "C_3") (pintype "passive"))
      (node (ref "R32") (pin "1") (pinfunction "1_1") (pintype "passive"))
    )
    (net (code "64") (name "Net-(Q32-E)") (class "Default")
      (node (ref "Q32") (pin "2") (pinfunction "E_2") (pintype "passive"))
      (node (ref "QI") (pin "7") (pinfunction "C4_7") (pintype "passive"))
      (node (ref "QI") (pin "8") (pinfunction "C4_8") (pintype "passive"))
    )
    (net (code "65") (name "Net-(Q35-C)") (class "Default")
      (node (ref "Q35") (pin "3") (pinfunction "C_3") (pintype "passive"))
      (node (ref "QI") (pin "14") (pinfunction "E2_14") (pintype "passive"))
      (node (ref "QI") (pin "16") (pinfunction "E1_16") (pintype "passive"))
    )
    (net (code "66") (name "Net-(Q35-E)") (class "Default")
      (node (ref "Q35") (pin "2") (pinfunction "E_2") (pintype "passive"))
      (node (ref "RV1") (pin "3") (pinfunction "C_3") (pintype "passive"))
    )
    (net (code "67") (name "Net-(Q36-C)") (class "Default")
      (node (ref "Q36") (pin "3") (pinfunction "C_3") (pintype "passive"))
      (node (ref "QI") (pin "10") (pinfunction "E4_10") (pintype "passive"))
      (node (ref "QI") (pin "12") (pinfunction "E3_12") (pintype "passive"))
    )
    (net (code "68") (name "Net-(Q36-E)") (class "Default")
      (node (ref "Q36") (pin "2") (pinfunction "E_2") (pintype "passive"))
      (node (ref "RV2") (pin "3") (pinfunction "C_3") (pintype "passive"))
    )
    (net (code "69") (name "Net-(Q37-E)") (class "Default")
      (node (ref "Q37") (pin "2") (pinfunction "E_2") (pintype "passive"))
      (node (ref "QI") (pin "1") (pinfunction "C1_1") (pintype "passive"))
      (node (ref "QI") (pin "2") (pinfunction "C1_2") (pintype "passive"))
    )
    (net (code "70") (name "Net-(Q38-E)") (class "Default")
      (node (ref "Q38") (pin "2") (pinfunction "E_2") (pintype "passive"))
      (node (ref "QI") (pin "5") (pinfunction "C3_5") (pintype "passive"))
      (node (ref "QI") (pin "6") (pinfunction "C3_6") (pintype "passive"))
    )
    (net (code "71") (name "Net-(QIA-B1)") (class "Default")
      (node (ref "CAI") (pin "2") (pinfunction "2_2") (pintype "passive"))
      (node (ref "QI") (pin "15") (pinfunction "B1_15") (pintype "passive"))
      (node (ref "RIOF") (pin "1") (pinfunction "1_1") (pintype "passive"))
    )
    (net (code "72") (name "Net-(QIB-B2)") (class "Default")
      (node (ref "CC7") (pin "1") (pinfunction "1_1") (pintype "passive"))
      (node (ref "QI") (pin "13") (pinfunction "B2_13") (pintype "passive"))
      (node (ref "QI") (pin "9") (pinfunction "B4_9") (pintype "passive"))
      (node (ref "RFB1") (pin "1") (pinfunction "1_1") (pintype "passive"))
      (node (ref "RFB2") (pin "2") (pinfunction "2_2") (pintype "passive"))
    )
    (net (code "73") (name "Net-(R11-Pad1)") (class "Default")
      (node (ref "R11") (pin "1") (pinfunction "1_1") (pintype "passive"))
      (node (ref "R12") (pin "2") (pinfunction "2_2") (pintype "passive"))
    )
    (net (code "74") (name "Net-(RV1-A)") (class "Default")
      (node (ref "R33") (pin "2") (pintype "passive"))
      (node (ref "RV1") (pin "1") (pinfunction "A_1") (pintype "passive"))
      (node (ref "RV1") (pin "2") (pinfunction "B_2") (pintype "passive"))
      (node (ref "TP9") (pin "1") (pintype "passive"))
    )
    (net (code "75") (name "Net-(RV2-A)") (class "Default")
      (node (ref "R34") (pin "2") (pintype "passive"))
      (node (ref "RV2") (pin "1") (pinfunction "A_1") (pintype "passive"))
      (node (ref "RV2") (pin "2") (pinfunction "B_2") (pintype "passive"))
      (node (ref "TP10") (pin "1") (pintype "passive"))
    )
    (net (code "76") (name "Net-(RVC1-C)") (class "Default")
      (node (ref "R35") (pin "1") (pinfunction "1_1") (pintype "passive"))
      (node (ref "RVC1") (pin "3") (pinfunction "C_3") (pintype "passive"))
    )
    (net (code "77") (name "Net-(RVC2-C)") (class "Default")
      (node (ref "R36") (pin "1") (pinfunction "1_1") (pintype "passive"))
      (node (ref "RVC2") (pin "3") (pinfunction "C_3") (pintype "passive"))
    )
    (net (code "78") (name "Net-(RVMV-B)") (class "Default")
      (node (ref "RVMV") (pin "2") (pinfunction "B_2") (pintype "passive"))
      (node (ref "RVMV") (pin "3") (pinfunction "C_3") (pintype "passive"))
    )
    (net (code "79") (name "unconnected-(Q36-B-Pad1)") (class "Default")
      (node (ref "Q36") (pin "1") (pinfunction "B_1") (pintype "passive"))
    )
    (net (code "80") (name "unconnected-(QIC-B3-Pad11)") (class "Default")
      (node (ref "QI") (pin "11") (pinfunction "B3_11") (pintype "passive"))
    )
    (net (code "81") (name "unconnected-(R20-Pad1)") (class "Default")
      (node (ref "R20") (pin "1") (pinfunction "1_1") (pintype "passive"))
    )
    (net (code "82") (name "unconnected-(RMVM-Pad2)") (class "Default")
      (node (ref "RMVM") (pin "2") (pinfunction "2_2") (pintype "passive"))
    )
  )
)
